# blimpy-2_1.net
KiCad netlist of a schematic drawn in EAGLE
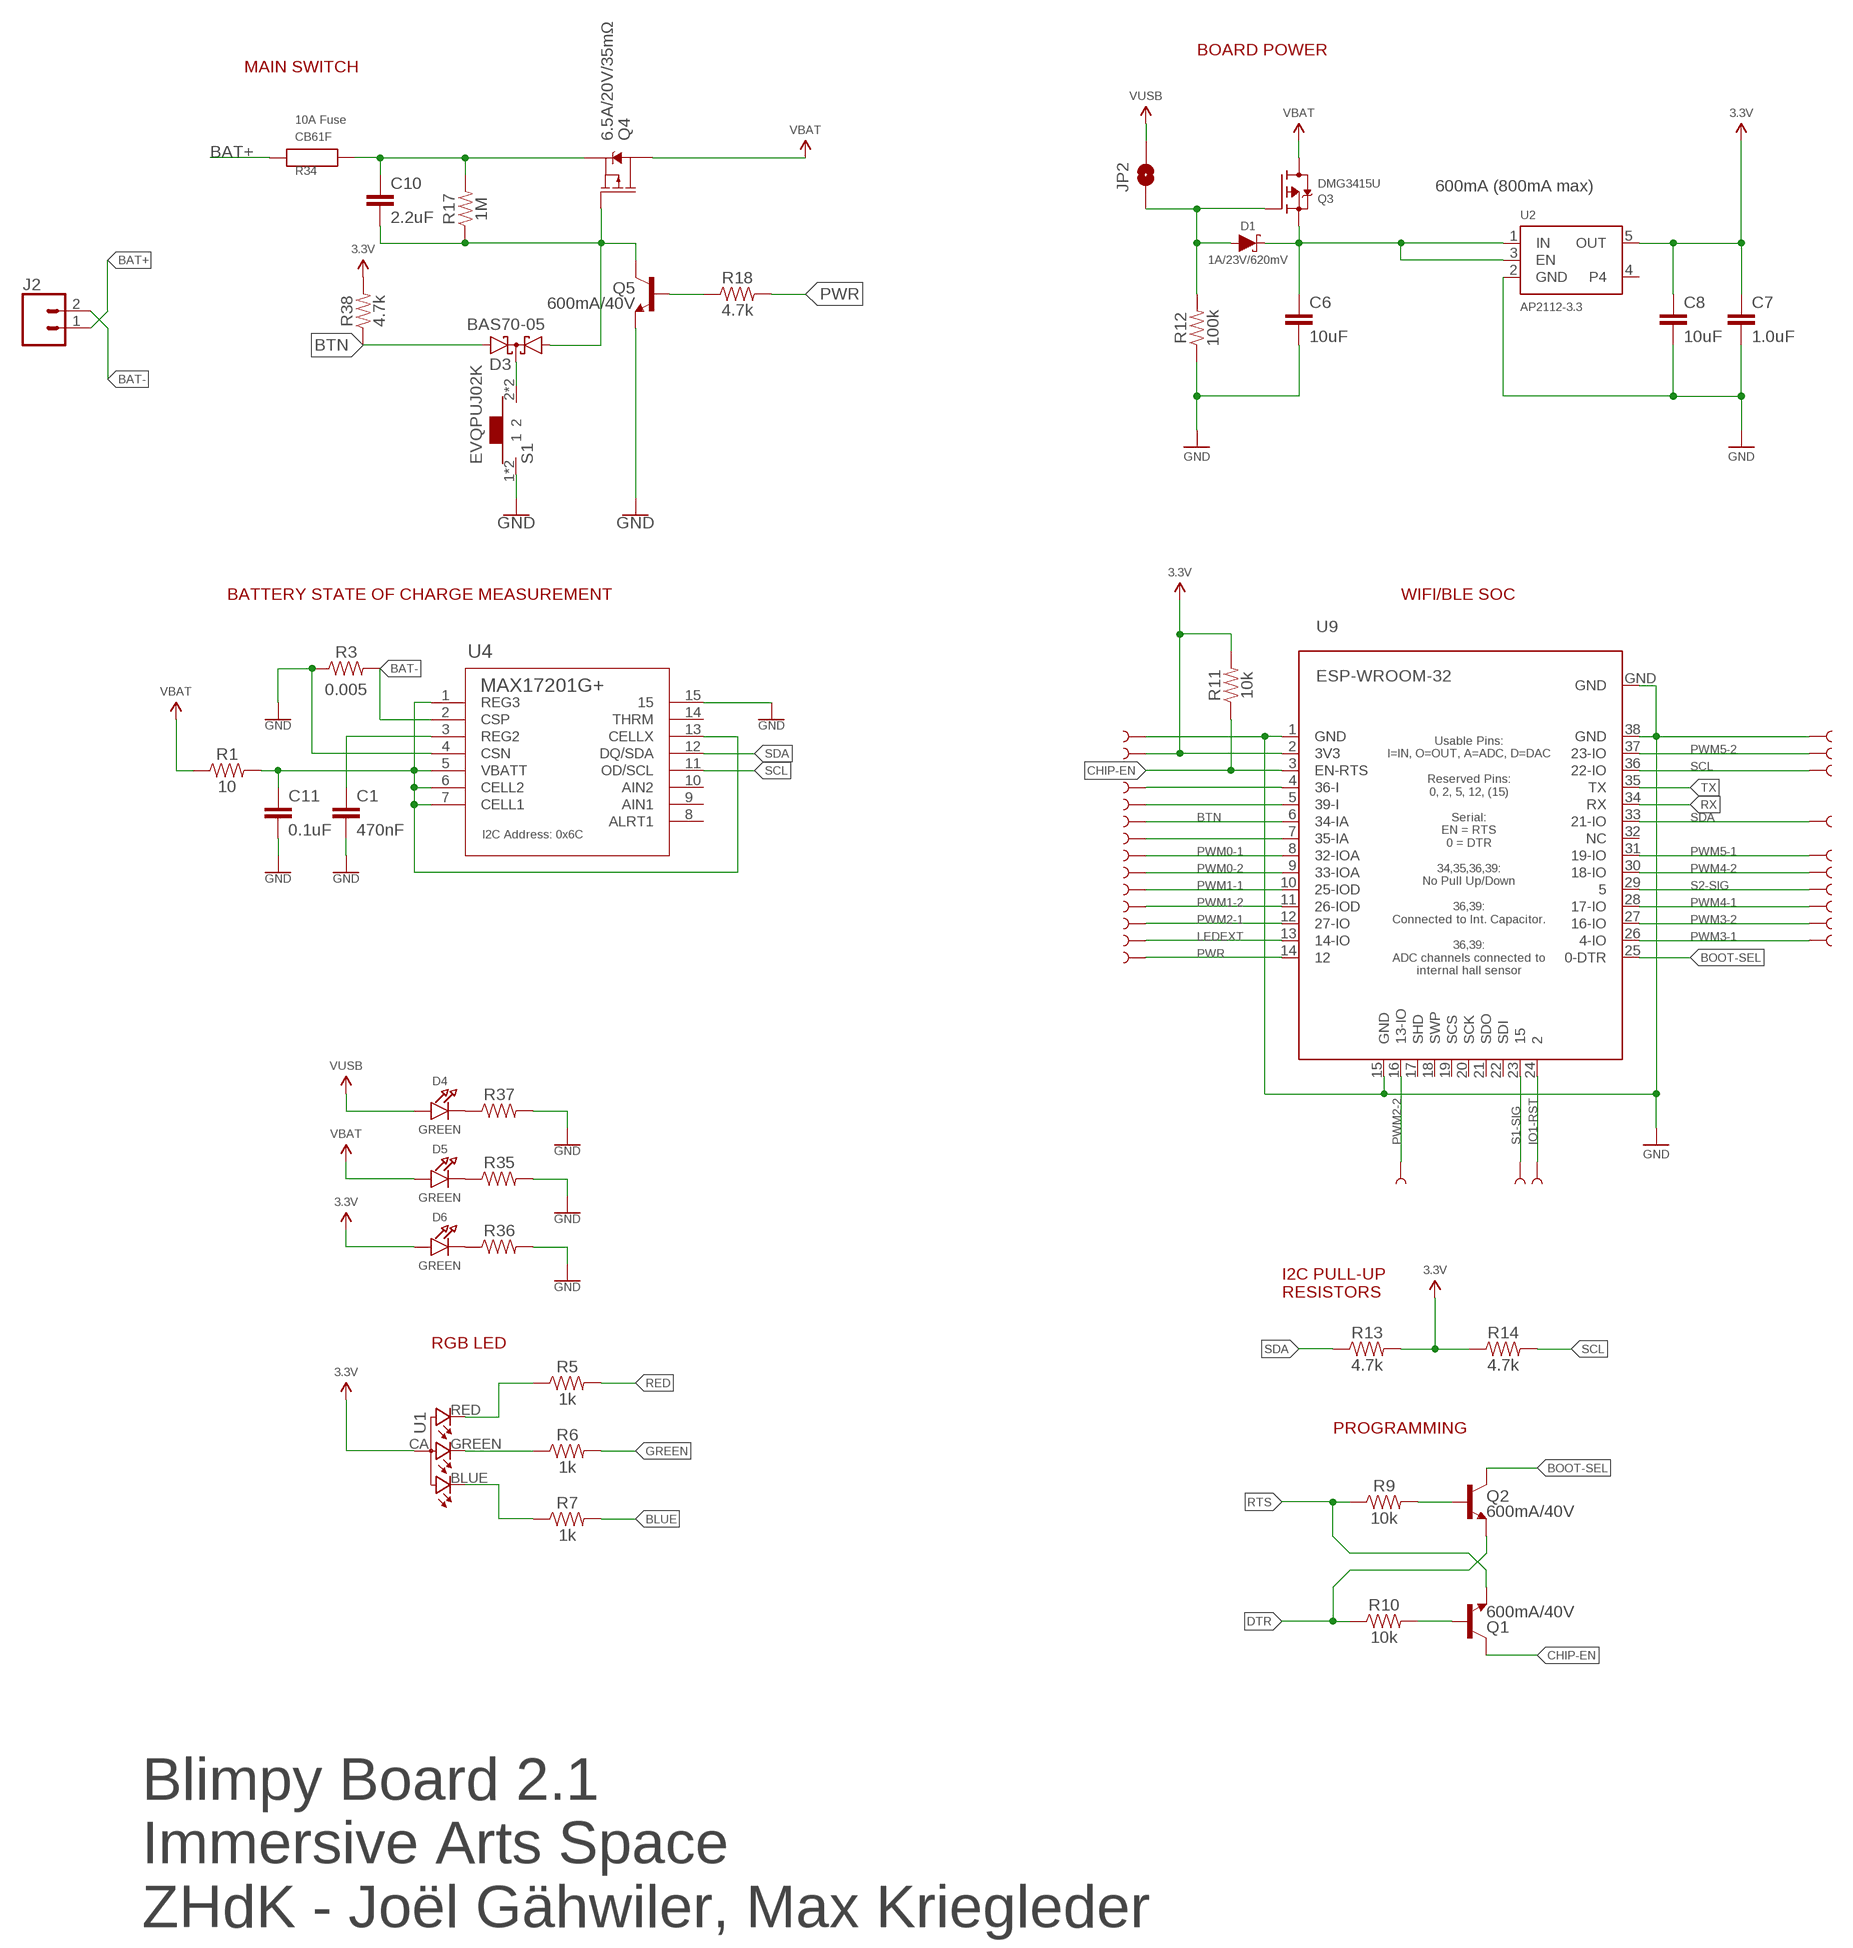
[diagram p0: schematic, sheet 1, part 1 of 2]
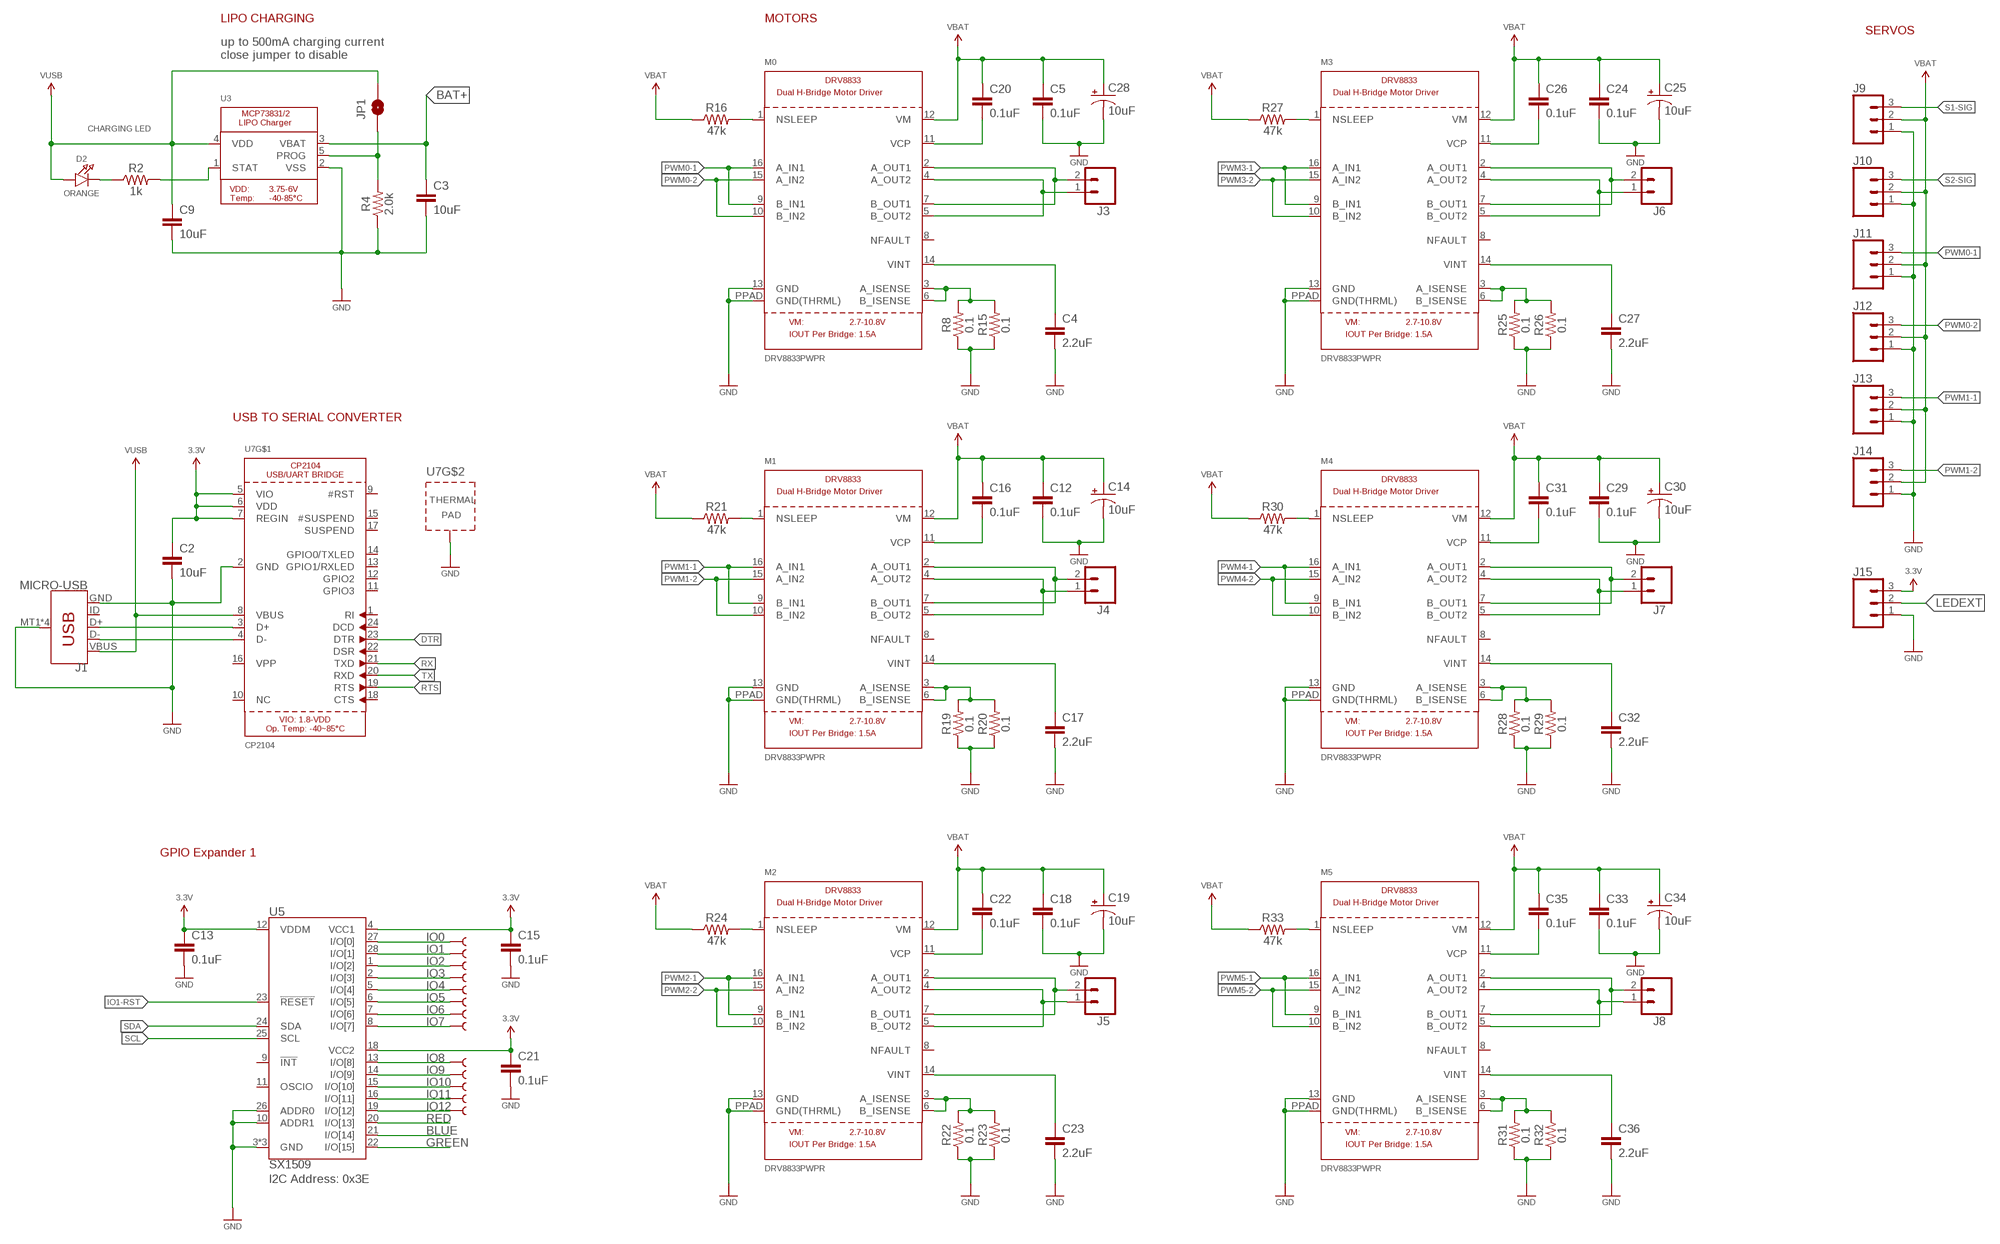
[diagram p1: schematic, sheet 1, part 2 of 2]

(export (version "E")
  (design (tool "Eeschema 10.0.6"))
  (components
    (comp (ref "C1")
      (value "470nF")
      (footprint "eagle-import:0603")
      (libsource (lib "eagle-import") (part "470NF-0608"))
    )
    (comp (ref "C2")
      (value "10uF")
      (footprint "eagle-import:0603")
      (libsource (lib "eagle-import") (part "10UF-0603-6.3V-20%"))
    )
    (comp (ref "C3")
      (value "10uF")
      (footprint "eagle-import:0603")
      (libsource (lib "eagle-import") (part "10UF-0603-6.3V-20%"))
    )
    (comp (ref "C4")
      (value "2.2uF")
      (footprint "eagle-import:0603")
      (libsource (lib "eagle-import") (part "2.2UF-0603-10V-20%"))
    )
    (comp (ref "C5")
      (value "0.1uF")
      (footprint "eagle-import:0603")
      (libsource (lib "eagle-import") (part "0.1UF-0603-25V-5%"))
    )
    (comp (ref "C6")
      (value "10uF")
      (footprint "eagle-import:0603")
      (libsource (lib "eagle-import") (part "10UF-0603-6.3V-20%"))
    )
    (comp (ref "C7")
      (value "1.0uF")
      (footprint "eagle-import:0603")
      (libsource (lib "eagle-import") (part "1.0UF-0603-16V-10%"))
    )
    (comp (ref "C8")
      (value "10uF")
      (footprint "eagle-import:0603")
      (libsource (lib "eagle-import") (part "10UF-0603-6.3V-20%"))
    )
    (comp (ref "C9")
      (value "10uF")
      (footprint "eagle-import:0603")
      (libsource (lib "eagle-import") (part "10UF-0603-6.3V-20%"))
    )
    (comp (ref "C10")
      (value "2.2uF")
      (footprint "eagle-import:0603")
      (libsource (lib "eagle-import") (part "2.2UF-0603-10V-20%"))
    )
    (comp (ref "C11")
      (value "0.1uF")
      (footprint "eagle-import:0603")
      (libsource (lib "eagle-import") (part "SparkFun-Capacitors_510_0.1UF-0603-25V-5%"))
    )
    (comp (ref "C12")
      (value "0.1uF")
      (footprint "eagle-import:0603")
      (libsource (lib "eagle-import") (part "0.1UF-0603-25V-5%"))
    )
    (comp (ref "C13")
      (value "0.1uF")
      (footprint "eagle-import:0603")
      (libsource (lib "eagle-import") (part "0.1UF-0603-25V-5%"))
    )
    (comp (ref "C14")
      (value "10uF")
      (footprint "eagle-import:EIA3216")
      (libsource (lib "eagle-import") (part "10UF-POLAR-EIA3216-16V-10%(TANT)"))
    )
    (comp (ref "C15")
      (value "0.1uF")
      (footprint "eagle-import:0603")
      (libsource (lib "eagle-import") (part "SparkFun-Capacitors_510_0.1UF-0603-25V-5%"))
    )
    (comp (ref "C16")
      (value "0.1uF")
      (footprint "eagle-import:0603")
      (libsource (lib "eagle-import") (part "0.1UF-0603-25V-5%"))
    )
    (comp (ref "C17")
      (value "2.2uF")
      (footprint "eagle-import:0603")
      (libsource (lib "eagle-import") (part "2.2UF-0603-10V-20%"))
    )
    (comp (ref "C18")
      (value "0.1uF")
      (footprint "eagle-import:0603")
      (libsource (lib "eagle-import") (part "0.1UF-0603-25V-5%"))
    )
    (comp (ref "C19")
      (value "10uF")
      (footprint "eagle-import:EIA3216")
      (libsource (lib "eagle-import") (part "10UF-POLAR-EIA3216-16V-10%(TANT)"))
    )
    (comp (ref "C20")
      (value "0.1uF")
      (footprint "eagle-import:0603")
      (libsource (lib "eagle-import") (part "0.1UF-0603-25V-5%"))
    )
    (comp (ref "C21")
      (value "0.1uF")
      (footprint "eagle-import:0603")
      (libsource (lib "eagle-import") (part "0.1UF-0603-25V-5%"))
    )
    (comp (ref "C22")
      (value "0.1uF")
      (footprint "eagle-import:0603")
      (libsource (lib "eagle-import") (part "0.1UF-0603-25V-5%"))
    )
    (comp (ref "C23")
      (value "2.2uF")
      (footprint "eagle-import:0603")
      (libsource (lib "eagle-import") (part "2.2UF-0603-10V-20%"))
    )
    (comp (ref "C24")
      (value "0.1uF")
      (footprint "eagle-import:0603")
      (libsource (lib "eagle-import") (part "0.1UF-0603-25V-5%"))
    )
    (comp (ref "C25")
      (value "10uF")
      (footprint "eagle-import:EIA3216")
      (libsource (lib "eagle-import") (part "10UF-POLAR-EIA3216-16V-10%(TANT)"))
    )
    (comp (ref "C26")
      (value "0.1uF")
      (footprint "eagle-import:0603")
      (libsource (lib "eagle-import") (part "0.1UF-0603-25V-5%"))
    )
    (comp (ref "C27")
      (value "2.2uF")
      (footprint "eagle-import:0603")
      (libsource (lib "eagle-import") (part "2.2UF-0603-10V-20%"))
    )
    (comp (ref "C28")
      (value "10uF")
      (footprint "eagle-import:EIA3216")
      (libsource (lib "eagle-import") (part "10UF-POLAR-EIA3216-16V-10%(TANT)"))
    )
    (comp (ref "C29")
      (value "0.1uF")
      (footprint "eagle-import:0603")
      (libsource (lib "eagle-import") (part "0.1UF-0603-25V-5%"))
    )
    (comp (ref "C30")
      (value "10uF")
      (footprint "eagle-import:EIA3216")
      (libsource (lib "eagle-import") (part "10UF-POLAR-EIA3216-16V-10%(TANT)"))
    )
    (comp (ref "C31")
      (value "0.1uF")
      (footprint "eagle-import:0603")
      (libsource (lib "eagle-import") (part "0.1UF-0603-25V-5%"))
    )
    (comp (ref "C32")
      (value "2.2uF")
      (footprint "eagle-import:0603")
      (libsource (lib "eagle-import") (part "2.2UF-0603-10V-20%"))
    )
    (comp (ref "C33")
      (value "0.1uF")
      (footprint "eagle-import:0603")
      (libsource (lib "eagle-import") (part "0.1UF-0603-25V-5%"))
    )
    (comp (ref "C34")
      (value "10uF")
      (footprint "eagle-import:EIA3216")
      (libsource (lib "eagle-import") (part "10UF-POLAR-EIA3216-16V-10%(TANT)"))
    )
    (comp (ref "C35")
      (value "0.1uF")
      (footprint "eagle-import:0603")
      (libsource (lib "eagle-import") (part "0.1UF-0603-25V-5%"))
    )
    (comp (ref "C36")
      (value "2.2uF")
      (footprint "eagle-import:0603")
      (libsource (lib "eagle-import") (part "2.2UF-0603-10V-20%"))
    )
    (comp (ref "D1")
      (value "1A/23V/620mV")
      (footprint "eagle-import:SOD-323")
      (libsource (lib "eagle-import") (part "DIODE-SCHOTTKY-BAT20J"))
    )
    (comp (ref "D2")
      (value "ORANGE")
      (footprint "eagle-import:CHIPLED_0805_NOOUTLINE")
      (libsource (lib "eagle-import") (part "LED0805_NOOUTLINE"))
    )
    (comp (ref "D3")
      (value "BAS70-05")
      (footprint "eagle-import:SOT23")
      (libsource (lib "eagle-import") (part "BAS70-05"))
    )
    (comp (ref "D4")
      (value "GREEN")
      (footprint "eagle-import:CHIPLED_0805_NOOUTLINE")
      (libsource (lib "eagle-import") (part "LED0805_NOOUTLINE"))
    )
    (comp (ref "D5")
      (value "GREEN")
      (footprint "eagle-import:CHIPLED_0805_NOOUTLINE")
      (libsource (lib "eagle-import") (part "LED0805_NOOUTLINE"))
    )
    (comp (ref "D6")
      (value "GREEN")
      (footprint "eagle-import:CHIPLED_0805_NOOUTLINE")
      (libsource (lib "eagle-import") (part "LED0805_NOOUTLINE"))
    )
    (comp (ref "J1")
      (value "MICRO-USB")
      (footprint "eagle-import:USB-MICROB")
      (libsource (lib "eagle-import") (part "USB_MICRO-B_SMT"))
    )
    (comp (ref "J2")
      (value "CONN_02PTH4")
      (footprint "eagle-import:1X02_XTRA_BIG")
      (libsource (lib "eagle-import") (part "CONN_02PTH4"))
    )
    (comp (ref "J3")
      (value "CONN_02-JST-2MM-SMT")
      (footprint "eagle-import:JST-2-SMD")
      (libsource (lib "eagle-import") (part "CONN_02-JST-2MM-SMT"))
    )
    (comp (ref "J4")
      (value "CONN_02-JST-2MM-SMT")
      (footprint "eagle-import:JST-2-SMD")
      (libsource (lib "eagle-import") (part "CONN_02-JST-2MM-SMT"))
    )
    (comp (ref "J5")
      (value "CONN_02-JST-2MM-SMT")
      (footprint "eagle-import:JST-2-SMD")
      (libsource (lib "eagle-import") (part "CONN_02-JST-2MM-SMT"))
    )
    (comp (ref "J6")
      (value "CONN_02-JST-2MM-SMT")
      (footprint "eagle-import:JST-2-SMD")
      (libsource (lib "eagle-import") (part "CONN_02-JST-2MM-SMT"))
    )
    (comp (ref "J7")
      (value "CONN_02-JST-2MM-SMT")
      (footprint "eagle-import:JST-2-SMD")
      (libsource (lib "eagle-import") (part "CONN_02-JST-2MM-SMT"))
    )
    (comp (ref "J8")
      (value "CONN_02-JST-2MM-SMT")
      (footprint "eagle-import:JST-2-SMD")
      (libsource (lib "eagle-import") (part "CONN_02-JST-2MM-SMT"))
    )
    (comp (ref "J9")
      (value "3-PIN SMD")
      (footprint "eagle-import:JST-3-SMD")
      (libsource (lib "eagle-import") (part "CONN_03JST-SMD"))
    )
    (comp (ref "J10")
      (value "3-PIN SMD")
      (footprint "eagle-import:JST-3-SMD")
      (libsource (lib "eagle-import") (part "CONN_03JST-SMD"))
    )
    (comp (ref "J11")
      (value "3-PIN SMD")
      (footprint "eagle-import:JST-3-SMD")
      (libsource (lib "eagle-import") (part "CONN_03JST-SMD"))
    )
    (comp (ref "J12")
      (value "3-PIN SMD")
      (footprint "eagle-import:JST-3-SMD")
      (libsource (lib "eagle-import") (part "CONN_03JST-SMD"))
    )
    (comp (ref "J13")
      (value "3-PIN SMD")
      (footprint "eagle-import:JST-3-SMD")
      (libsource (lib "eagle-import") (part "CONN_03JST-SMD"))
    )
    (comp (ref "J14")
      (value "3-PIN SMD")
      (footprint "eagle-import:JST-3-SMD")
      (libsource (lib "eagle-import") (part "CONN_03JST-SMD"))
    )
    (comp (ref "J15")
      (value "3-PIN SMD")
      (footprint "eagle-import:JST-3-SMD")
      (libsource (lib "eagle-import") (part "CONN_03JST-SMD"))
    )
    (comp (ref "JP1")
      (value "JUMPER-SMT_2_NO_SILK")
      (footprint "eagle-import:SMT-JUMPER_2_NO_SILK")
      (libsource (lib "eagle-import") (part "JUMPER-SMT_2_NO_SILK"))
    )
    (comp (ref "JP2")
      (value "JUMPER-SMT_2_NO_SILK")
      (footprint "eagle-import:SMT-JUMPER_2_NO_SILK")
      (libsource (lib "eagle-import") (part "JUMPER-SMT_2_NO_SILK"))
    )
    (comp (ref "M0")
      (value "DRV8833PWPR")
      (footprint "eagle-import:HTSSOP16")
      (libsource (lib "eagle-import") (part "DRV8833"))
    )
    (comp (ref "M1")
      (value "DRV8833PWPR")
      (footprint "eagle-import:HTSSOP16")
      (libsource (lib "eagle-import") (part "DRV8833"))
    )
    (comp (ref "M2")
      (value "DRV8833PWPR")
      (footprint "eagle-import:HTSSOP16")
      (libsource (lib "eagle-import") (part "DRV8833"))
    )
    (comp (ref "M3")
      (value "DRV8833PWPR")
      (footprint "eagle-import:HTSSOP16")
      (libsource (lib "eagle-import") (part "DRV8833"))
    )
    (comp (ref "M4")
      (value "DRV8833PWPR")
      (footprint "eagle-import:HTSSOP16")
      (libsource (lib "eagle-import") (part "DRV8833"))
    )
    (comp (ref "M5")
      (value "DRV8833PWPR")
      (footprint "eagle-import:HTSSOP16")
      (libsource (lib "eagle-import") (part "DRV8833"))
    )
    (comp (ref "Q1")
      (value "600mA/40V")
      (footprint "eagle-import:SOT23-3")
      (libsource (lib "eagle-import") (part "TRANS_NPN-MMBT2222AL"))
    )
    (comp (ref "Q2")
      (value "600mA/40V")
      (footprint "eagle-import:SOT23-3")
      (libsource (lib "eagle-import") (part "TRANS_NPN-MMBT2222AL"))
    )
    (comp (ref "Q3")
      (value "DMG3415U")
      (footprint "eagle-import:SOT23-R")
      (libsource (lib "eagle-import") (part "MOSFET-P"))
    )
    (comp (ref "Q4")
      (value "6.5A/20V/35mΩ")
      (footprint "eagle-import:SO08")
      (libsource (lib "eagle-import") (part "MOSFET_PCH-NDS8434"))
    )
    (comp (ref "Q5")
      (value "600mA/40V")
      (footprint "eagle-import:SOT23-3")
      (libsource (lib "eagle-import") (part "TRANS_NPN-MMBT2222AL"))
    )
    (comp (ref "R1")
      (value "10")
      (footprint "eagle-import:0603")
      (libsource (lib "eagle-import") (part "10OHM-0603-1/10W-1%"))
    )
    (comp (ref "R2")
      (value "1k")
      (footprint "eagle-import:0603")
      (libsource (lib "eagle-import") (part "1KOHM-0603-1/10W-1%"))
    )
    (comp (ref "R3")
      (value "0.005")
      (footprint "eagle-import:1206")
      (libsource (lib "eagle-import") (part "RESISTOR1206"))
    )
    (comp (ref "R4")
      (value "2.0k")
      (footprint "eagle-import:0603")
      (libsource (lib "eagle-import") (part "2.0KOHM-0603-1/10W-5%"))
    )
    (comp (ref "R5")
      (value "1k")
      (footprint "eagle-import:0603")
      (libsource (lib "eagle-import") (part "1KOHM-0603-1/10W-1%"))
    )
    (comp (ref "R6")
      (value "1k")
      (footprint "eagle-import:0603")
      (libsource (lib "eagle-import") (part "1KOHM-0603-1/10W-1%"))
    )
    (comp (ref "R7")
      (value "1k")
      (footprint "eagle-import:0603")
      (libsource (lib "eagle-import") (part "1KOHM-0603-1/10W-1%"))
    )
    (comp (ref "R8")
      (value "0.1")
      (footprint "eagle-import:1206")
      (libsource (lib "eagle-import") (part "RESISTOR1206"))
    )
    (comp (ref "R9")
      (value "10k")
      (footprint "eagle-import:0603")
      (libsource (lib "eagle-import") (part "10KOHM-0603-1/10W-1%"))
    )
    (comp (ref "R10")
      (value "10k")
      (footprint "eagle-import:0603")
      (libsource (lib "eagle-import") (part "10KOHM-0603-1/10W-1%"))
    )
    (comp (ref "R11")
      (value "10k")
      (footprint "eagle-import:0603")
      (libsource (lib "eagle-import") (part "10KOHM-0603-1/10W-1%"))
    )
    (comp (ref "R12")
      (value "100k")
      (footprint "eagle-import:0603")
      (libsource (lib "eagle-import") (part "100KOHM-0603-1/10W-1%"))
    )
    (comp (ref "R13")
      (value "4.7k")
      (footprint "eagle-import:0603")
      (libsource (lib "eagle-import") (part "4.7KOHM-0603-1/10W-1%"))
    )
    (comp (ref "R14")
      (value "4.7k")
      (footprint "eagle-import:0603")
      (libsource (lib "eagle-import") (part "4.7KOHM-0603-1/10W-1%"))
    )
    (comp (ref "R15")
      (value "0.1")
      (footprint "eagle-import:1206")
      (libsource (lib "eagle-import") (part "RESISTOR1206"))
    )
    (comp (ref "R16")
      (value "47k")
      (footprint "eagle-import:0603")
      (libsource (lib "eagle-import") (part "47KOHM-0603-1/10W-1%"))
    )
    (comp (ref "R17")
      (value "1M")
      (footprint "eagle-import:0603")
      (libsource (lib "eagle-import") (part "1MOHM-0603-1/4W-5%"))
    )
    (comp (ref "R18")
      (value "4.7k")
      (footprint "eagle-import:0603")
      (libsource (lib "eagle-import") (part "SparkFun-Resistors_532_4.7KOHM-0603-1/10W-1%"))
    )
    (comp (ref "R19")
      (value "0.1")
      (footprint "eagle-import:1206")
      (libsource (lib "eagle-import") (part "RESISTOR1206"))
    )
    (comp (ref "R20")
      (value "0.1")
      (footprint "eagle-import:1206")
      (libsource (lib "eagle-import") (part "RESISTOR1206"))
    )
    (comp (ref "R21")
      (value "47k")
      (footprint "eagle-import:0603")
      (libsource (lib "eagle-import") (part "47KOHM-0603-1/10W-1%"))
    )
    (comp (ref "R22")
      (value "0.1")
      (footprint "eagle-import:1206")
      (libsource (lib "eagle-import") (part "RESISTOR1206"))
    )
    (comp (ref "R23")
      (value "0.1")
      (footprint "eagle-import:1206")
      (libsource (lib "eagle-import") (part "RESISTOR1206"))
    )
    (comp (ref "R24")
      (value "47k")
      (footprint "eagle-import:0603")
      (libsource (lib "eagle-import") (part "47KOHM-0603-1/10W-1%"))
    )
    (comp (ref "R25")
      (value "0.1")
      (footprint "eagle-import:1206")
      (libsource (lib "eagle-import") (part "RESISTOR1206"))
    )
    (comp (ref "R26")
      (value "0.1")
      (footprint "eagle-import:1206")
      (libsource (lib "eagle-import") (part "RESISTOR1206"))
    )
    (comp (ref "R27")
      (value "47k")
      (footprint "eagle-import:0603")
      (libsource (lib "eagle-import") (part "47KOHM-0603-1/10W-1%"))
    )
    (comp (ref "R28")
      (value "0.1")
      (footprint "eagle-import:1206")
      (libsource (lib "eagle-import") (part "RESISTOR1206"))
    )
    (comp (ref "R29")
      (value "0.1")
      (footprint "eagle-import:1206")
      (libsource (lib "eagle-import") (part "RESISTOR1206"))
    )
    (comp (ref "R30")
      (value "47k")
      (footprint "eagle-import:0603")
      (libsource (lib "eagle-import") (part "47KOHM-0603-1/10W-1%"))
    )
    (comp (ref "R31")
      (value "0.1")
      (footprint "eagle-import:1206")
      (libsource (lib "eagle-import") (part "RESISTOR1206"))
    )
    (comp (ref "R32")
      (value "0.1")
      (footprint "eagle-import:1206")
      (libsource (lib "eagle-import") (part "RESISTOR1206"))
    )
    (comp (ref "R33")
      (value "47k")
      (footprint "eagle-import:0603")
      (libsource (lib "eagle-import") (part "47KOHM-0603-1/10W-1%"))
    )
    (comp (ref "R34")
      (value "CB61F")
      (footprint "eagle-import:CB61F")
      (libsource (lib "eagle-import") (part "CB61F"))
    )
    (comp (ref "R35")
      (value "RESISTOR0603")
      (footprint "eagle-import:0603")
      (libsource (lib "eagle-import") (part "RESISTOR0603"))
    )
    (comp (ref "R36")
      (value "RESISTOR0603")
      (footprint "eagle-import:0603")
      (libsource (lib "eagle-import") (part "RESISTOR0603"))
    )
    (comp (ref "R37")
      (value "RESISTOR0603")
      (footprint "eagle-import:0603")
      (libsource (lib "eagle-import") (part "RESISTOR0603"))
    )
    (comp (ref "R38")
      (value "4.7k")
      (footprint "eagle-import:0603")
      (libsource (lib "eagle-import") (part "1MOHM-0603-1/4W-5%"))
    )
    (comp (ref "S1")
      (value "EVQPUJ02K")
      (footprint "eagle-import:EVQPUJ02K")
      (libsource (lib "eagle-import") (part "EVQPUJ02K"))
    )
    (comp (ref "TP1")
      (value "TEST-POINT3")
      (footprint "eagle-import:PAD.03X.03")
      (libsource (lib "eagle-import") (part "TEST-POINT3"))
    )
    (comp (ref "TP2")
      (value "TEST-POINT3")
      (footprint "eagle-import:PAD.03X.03")
      (libsource (lib "eagle-import") (part "TEST-POINT3"))
    )
    (comp (ref "TP3")
      (value "TEST-POINT3")
      (footprint "eagle-import:PAD.03X.03")
      (libsource (lib "eagle-import") (part "TEST-POINT3"))
    )
    (comp (ref "TP4")
      (value "TEST-POINT3")
      (footprint "eagle-import:PAD.03X.03")
      (libsource (lib "eagle-import") (part "TEST-POINT3"))
    )
    (comp (ref "TP5")
      (value "TEST-POINT3")
      (footprint "eagle-import:PAD.03X.03")
      (libsource (lib "eagle-import") (part "TEST-POINT3"))
    )
    (comp (ref "TP6")
      (value "TEST-POINT3")
      (footprint "eagle-import:PAD.03X.03")
      (libsource (lib "eagle-import") (part "TEST-POINT3"))
    )
    (comp (ref "TP7")
      (value "TEST-POINT3")
      (footprint "eagle-import:PAD.03X.03")
      (libsource (lib "eagle-import") (part "TEST-POINT3"))
    )
    (comp (ref "TP8")
      (value "TEST-POINT3")
      (footprint "eagle-import:PAD.03X.03")
      (libsource (lib "eagle-import") (part "TEST-POINT3"))
    )
    (comp (ref "TP9")
      (value "TEST-POINT3")
      (footprint "eagle-import:PAD.03X.03")
      (libsource (lib "eagle-import") (part "TEST-POINT3"))
    )
    (comp (ref "TP10")
      (value "TEST-POINT3")
      (footprint "eagle-import:PAD.03X.03")
      (libsource (lib "eagle-import") (part "TEST-POINT3"))
    )
    (comp (ref "TP11")
      (value "TEST-POINT3")
      (footprint "eagle-import:PAD.03X.03")
      (libsource (lib "eagle-import") (part "TEST-POINT3"))
    )
    (comp (ref "TP12")
      (value "TEST-POINT3")
      (footprint "eagle-import:PAD.03X.03")
      (libsource (lib "eagle-import") (part "TEST-POINT3"))
    )
    (comp (ref "TP13")
      (value "TEST-POINT3")
      (footprint "eagle-import:PAD.03X.03")
      (libsource (lib "eagle-import") (part "TEST-POINT3"))
    )
    (comp (ref "TP14")
      (value "TEST-POINT3")
      (footprint "eagle-import:PAD.03X.03")
      (libsource (lib "eagle-import") (part "TEST-POINT3"))
    )
    (comp (ref "TP15")
      (value "TEST-POINT3")
      (footprint "eagle-import:PAD.03X.03")
      (libsource (lib "eagle-import") (part "TEST-POINT3"))
    )
    (comp (ref "TP16")
      (value "TEST-POINT3")
      (footprint "eagle-import:PAD.03X.03")
      (libsource (lib "eagle-import") (part "TEST-POINT3"))
    )
    (comp (ref "TP17")
      (value "TEST-POINT3")
      (footprint "eagle-import:PAD.03X.03")
      (libsource (lib "eagle-import") (part "TEST-POINT3"))
    )
    (comp (ref "TP18")
      (value "TEST-POINT3")
      (footprint "eagle-import:PAD.03X.03")
      (libsource (lib "eagle-import") (part "TEST-POINT3"))
    )
    (comp (ref "TP19")
      (value "TEST-POINT3")
      (footprint "eagle-import:PAD.03X.03")
      (libsource (lib "eagle-import") (part "TEST-POINT3"))
    )
    (comp (ref "TP20")
      (value "TEST-POINT3")
      (footprint "eagle-import:PAD.03X.03")
      (libsource (lib "eagle-import") (part "TEST-POINT3"))
    )
    (comp (ref "TP21")
      (value "TEST-POINT3")
      (footprint "eagle-import:PAD.03X.03")
      (libsource (lib "eagle-import") (part "TEST-POINT3"))
    )
    (comp (ref "TP22")
      (value "TEST-POINT3")
      (footprint "eagle-import:PAD.03X.03")
      (libsource (lib "eagle-import") (part "TEST-POINT3"))
    )
    (comp (ref "TP23")
      (value "TEST-POINT3")
      (footprint "eagle-import:PAD.03X.03")
      (libsource (lib "eagle-import") (part "TEST-POINT3"))
    )
    (comp (ref "TP24")
      (value "TEST-POINT3")
      (footprint "eagle-import:PAD.03X.03")
      (libsource (lib "eagle-import") (part "TEST-POINT3"))
    )
    (comp (ref "TP25")
      (value "TEST-POINT3")
      (footprint "eagle-import:PAD.03X.03")
      (libsource (lib "eagle-import") (part "TEST-POINT3"))
    )
    (comp (ref "TP26")
      (value "TEST-POINT3")
      (footprint "eagle-import:PAD.03X.03")
      (libsource (lib "eagle-import") (part "TEST-POINT3"))
    )
    (comp (ref "TP27")
      (value "TEST-POINT3")
      (footprint "eagle-import:PAD.03X.03")
      (libsource (lib "eagle-import") (part "TEST-POINT3"))
    )
    (comp (ref "TP28")
      (value "TEST-POINT3")
      (footprint "eagle-import:PAD.03X.03")
      (libsource (lib "eagle-import") (part "TEST-POINT3"))
    )
    (comp (ref "TP29")
      (value "TEST-POINT3")
      (footprint "eagle-import:PAD.03X.03")
      (libsource (lib "eagle-import") (part "TEST-POINT3"))
    )
    (comp (ref "TP30")
      (value "TEST-POINT3")
      (footprint "eagle-import:PAD.03X.03")
      (libsource (lib "eagle-import") (part "TEST-POINT3"))
    )
    (comp (ref "TP31")
      (value "TEST-POINT3")
      (footprint "eagle-import:PAD.03X.03")
      (libsource (lib "eagle-import") (part "TEST-POINT3"))
    )
    (comp (ref "TP32")
      (value "TEST-POINT3")
      (footprint "eagle-import:PAD.03X.03")
      (libsource (lib "eagle-import") (part "TEST-POINT3"))
    )
    (comp (ref "TP33")
      (value "TEST-POINT3")
      (footprint "eagle-import:PAD.03X.03")
      (libsource (lib "eagle-import") (part "TEST-POINT3"))
    )
    (comp (ref "TP34")
      (value "TEST-POINT3")
      (footprint "eagle-import:PAD.03X.03")
      (libsource (lib "eagle-import") (part "TEST-POINT3"))
    )
    (comp (ref "TP35")
      (value "TEST-POINT3")
      (footprint "eagle-import:PAD.03X.03")
      (libsource (lib "eagle-import") (part "TEST-POINT3"))
    )
    (comp (ref "TP36")
      (value "TEST-POINT3")
      (footprint "eagle-import:PAD.03X.03")
      (libsource (lib "eagle-import") (part "TEST-POINT3"))
    )
    (comp (ref "TP37")
      (value "TEST-POINT3")
      (footprint "eagle-import:PAD.03X.03")
      (libsource (lib "eagle-import") (part "TEST-POINT3"))
    )
    (comp (ref "TP38")
      (value "TEST-POINT3")
      (footprint "eagle-import:PAD.03X.03")
      (libsource (lib "eagle-import") (part "TEST-POINT3"))
    )
    (comp (ref "TP39")
      (value "TEST-POINT3")
      (footprint "eagle-import:PAD.03X.03")
      (libsource (lib "eagle-import") (part "TEST-POINT3"))
    )
    (comp (ref "U1")
      (value "PARTICLE_RGB-LED-CLMVB-FKARGB")
      (footprint "eagle-import:PARTICLE_PLCC4-2MM-RGB")
      (libsource (lib "eagle-import") (part "PARTICLE_RGB-LED-CLMVB-FKARGB"))
    )
    (comp (ref "U2")
      (value "AP2112-3.3")
      (footprint "eagle-import:SOT23-5")
      (libsource (lib "eagle-import") (part "VREG_SOT23-5"))
    )
    (comp (ref "U3")
      (value "MICROBUILDER_MCP73831/2")
      (footprint "eagle-import:MICROBUILDER_SOT23-5")
      (libsource (lib "eagle-import") (part "MICROBUILDER_MCP73831/2"))
    )
    (comp (ref "U4")
      (value "MAX17201G+")
      (footprint "eagle-import:21-0137I_T1433-1_MXM")
      (fields (field (name "COPYRIGHT") "Copyright (C) 2018 Accelerated Designs. All rights reserved"))
      (libsource (lib "eagle-import") (part "MAX17201G+"))
    )
    (comp (ref "U5")
      (value "SX1509")
      (footprint "eagle-import:QFN-28")
      (libsource (lib "eagle-import") (part "SX1509"))
    )
    (comp (ref "U7")
      (value "CP2104")
      (footprint "eagle-import:QFN24_4MM_SMSC")
      (libsource (lib "eagle-import") (part "CP2104"))
    )
    (comp (ref "U9")
      (value "ESP-WROOM-32")
      (footprint "eagle-import:ESP-WROOM-32")
      (libsource (lib "eagle-import") (part "ESP-WROOM-32"))
    )
  )
  (nets
    (net (code "1") (name "/IO0") (class "Default")
      (node (ref "TP27") (pin "P$1") (pinfunction "1_P$1") (pintype "bidirectional"))
      (node (ref "U5") (pin "27") (pinfunction "I/O[0]_27") (pintype "bidirectional"))
    )
    (net (code "2") (name "/IO1") (class "Default")
      (node (ref "TP28") (pin "P$1") (pinfunction "1_P$1") (pintype "bidirectional"))
      (node (ref "U5") (pin "28") (pinfunction "I/O[1]_28") (pintype "bidirectional"))
    )
    (net (code "3") (name "/IO2") (class "Default")
      (node (ref "TP29") (pin "P$1") (pinfunction "1_P$1") (pintype "bidirectional"))
      (node (ref "U5") (pin "1") (pinfunction "I/O[2]_1") (pintype "bidirectional"))
    )
    (net (code "4") (name "/IO3") (class "Default")
      (node (ref "TP30") (pin "P$1") (pinfunction "1_P$1") (pintype "bidirectional"))
      (node (ref "U5") (pin "2") (pinfunction "I/O[3]_2") (pintype "bidirectional"))
    )
    (net (code "5") (name "/IO4") (class "Default")
      (node (ref "TP31") (pin "P$1") (pinfunction "1_P$1") (pintype "bidirectional"))
      (node (ref "U5") (pin "5") (pinfunction "I/O[4]_5") (pintype "bidirectional"))
    )
    (net (code "6") (name "/IO5") (class "Default")
      (node (ref "TP32") (pin "P$1") (pinfunction "1_P$1") (pintype "bidirectional"))
      (node (ref "U5") (pin "6") (pinfunction "I/O[5]_6") (pintype "bidirectional"))
    )
    (net (code "7") (name "/IO6") (class "Default")
      (node (ref "TP33") (pin "P$1") (pinfunction "1_P$1") (pintype "bidirectional"))
      (node (ref "U5") (pin "7") (pinfunction "I/O[6]_7") (pintype "bidirectional"))
    )
    (net (code "8") (name "/IO7") (class "Default")
      (node (ref "TP34") (pin "P$1") (pinfunction "1_P$1") (pintype "bidirectional"))
      (node (ref "U5") (pin "8") (pinfunction "I/O[7]_8") (pintype "bidirectional"))
    )
    (net (code "9") (name "/IO8") (class "Default")
      (node (ref "TP35") (pin "P$1") (pinfunction "1_P$1") (pintype "bidirectional"))
      (node (ref "U5") (pin "13") (pinfunction "I/O[8]_13") (pintype "bidirectional"))
    )
    (net (code "10") (name "/IO9") (class "Default")
      (node (ref "TP36") (pin "P$1") (pinfunction "1_P$1") (pintype "bidirectional"))
      (node (ref "U5") (pin "14") (pinfunction "I/O[9]_14") (pintype "bidirectional"))
    )
    (net (code "11") (name "/IO10") (class "Default")
      (node (ref "TP37") (pin "P$1") (pinfunction "1_P$1") (pintype "bidirectional"))
      (node (ref "U5") (pin "15") (pinfunction "I/O[10]_15") (pintype "bidirectional"))
    )
    (net (code "12") (name "/IO11") (class "Default")
      (node (ref "TP38") (pin "P$1") (pinfunction "1_P$1") (pintype "bidirectional"))
      (node (ref "U5") (pin "16") (pinfunction "I/O[11]_16") (pintype "bidirectional"))
    )
    (net (code "13") (name "/IO12") (class "Default")
      (node (ref "TP39") (pin "P$1") (pinfunction "1_P$1") (pintype "bidirectional"))
      (node (ref "U5") (pin "19") (pinfunction "I/O[12]_19") (pintype "bidirectional"))
    )
    (net (code "14") (name "3.3V") (class "Default")
      (node (ref "C13") (pin "1") (pinfunction "1_1") (pintype "passive"))
      (node (ref "C15") (pin "1") (pinfunction "1_1") (pintype "passive"))
      (node (ref "C2") (pin "1") (pinfunction "1_1") (pintype "passive"))
      (node (ref "C21") (pin "1") (pinfunction "1_1") (pintype "passive"))
      (node (ref "C7") (pin "1") (pinfunction "1_1") (pintype "passive"))
      (node (ref "C8") (pin "1") (pinfunction "1_1") (pintype "passive"))
      (node (ref "D6") (pin "A") (pinfunction "A_A") (pintype "passive"))
      (node (ref "J15") (pin "3") (pinfunction "3_3") (pintype "passive"))
      (node (ref "R11") (pin "2") (pinfunction "2_2") (pintype "passive"))
      (node (ref "R13") (pin "2") (pinfunction "2_2") (pintype "passive"))
      (node (ref "R14") (pin "1") (pinfunction "1_1") (pintype "passive"))
      (node (ref "R38") (pin "2") (pinfunction "2_2") (pintype "passive"))
      (node (ref "TP11") (pin "P$1") (pinfunction "1_P$1") (pintype "bidirectional"))
      (node (ref "U1") (pin "CA") (pinfunction "1_CA") (pintype "passive"))
      (node (ref "U2") (pin "5") (pinfunction "OUT_5") (pintype "power_in"))
      (node (ref "U5") (pin "12") (pinfunction "VDDM_12") (pintype "bidirectional"))
      (node (ref "U5") (pin "18") (pinfunction "VCC2_18") (pintype "bidirectional"))
      (node (ref "U5") (pin "4") (pinfunction "VCC1_4") (pintype "bidirectional"))
      (node (ref "U7") (pin "5") (pinfunction "VIO_5") (pintype "power_in"))
      (node (ref "U7") (pin "6") (pinfunction "VDD_6") (pintype "power_in"))
      (node (ref "U7") (pin "7") (pinfunction "REGIN_7") (pintype "power_in"))
      (node (ref "U9") (pin "2") (pinfunction "3V3_2") (pintype "bidirectional"))
    )
    (net (code "15") (name "BAT+") (class "Default")
      (node (ref "C3") (pin "1") (pinfunction "1_1") (pintype "passive"))
      (node (ref "J2") (pin "1") (pinfunction "1_1") (pintype "passive"))
      (node (ref "R34") (pin "1") (pinfunction "1_1") (pintype "passive"))
      (node (ref "U3") (pin "3") (pinfunction "VBAT_3") (pintype "power_in"))
    )
    (net (code "16") (name "BAT-") (class "Default")
      (node (ref "J2") (pin "2") (pinfunction "2_2") (pintype "passive"))
      (node (ref "R3") (pin "2") (pinfunction "2_2") (pintype "passive"))
      (node (ref "U4") (pin "2") (pinfunction "CSP_2") (pintype "passive"))
    )
    (net (code "17") (name "BLUE") (class "Default")
      (node (ref "R7") (pin "2") (pinfunction "2_2") (pintype "passive"))
      (node (ref "U5") (pin "21") (pinfunction "I/O[14]_21") (pintype "bidirectional"))
    )
    (net (code "18") (name "BOOT-SEL") (class "Default")
      (node (ref "Q2") (pin "3") (pinfunction "C_3") (pintype "passive"))
      (node (ref "U9") (pin "25") (pinfunction "0-DTR_25") (pintype "bidirectional"))
    )
    (net (code "19") (name "BTN") (class "Default")
      (node (ref "D3") (pin "2") (pinfunction "A2_2") (pintype "passive"))
      (node (ref "R38") (pin "1") (pinfunction "1_1") (pintype "passive"))
      (node (ref "TP8") (pin "P$1") (pinfunction "1_P$1") (pintype "bidirectional"))
      (node (ref "U9") (pin "6") (pinfunction "34-IA_6") (pintype "bidirectional"))
    )
    (net (code "20") (name "CHIP-EN") (class "Default")
      (node (ref "Q1") (pin "3") (pinfunction "C_3") (pintype "passive"))
      (node (ref "R11") (pin "1") (pinfunction "1_1") (pintype "passive"))
      (node (ref "U9") (pin "3") (pinfunction "EN-RTS_3") (pintype "bidirectional"))
    )
    (net (code "21") (name "DTR") (class "Default")
      (node (ref "Q2") (pin "2") (pinfunction "E_2") (pintype "passive"))
      (node (ref "R10") (pin "1") (pinfunction "1_1") (pintype "passive"))
      (node (ref "U7") (pin "23") (pinfunction "DTR_23") (pintype "output"))
    )
    (net (code "22") (name "GND") (class "Default")
      (node (ref "C1") (pin "2") (pinfunction "2_2") (pintype "passive"))
      (node (ref "C11") (pin "2") (pinfunction "2_2") (pintype "passive"))
      (node (ref "C12") (pin "2") (pinfunction "2_2") (pintype "passive"))
      (node (ref "C13") (pin "2") (pinfunction "2_2") (pintype "passive"))
      (node (ref "C14") (pin "-") (pinfunction "-_-") (pintype "passive"))
      (node (ref "C15") (pin "2") (pinfunction "2_2") (pintype "passive"))
      (node (ref "C17") (pin "2") (pinfunction "2_2") (pintype "passive"))
      (node (ref "C18") (pin "2") (pinfunction "2_2") (pintype "passive"))
      (node (ref "C19") (pin "-") (pinfunction "-_-") (pintype "passive"))
      (node (ref "C2") (pin "2") (pinfunction "2_2") (pintype "passive"))
      (node (ref "C21") (pin "2") (pinfunction "2_2") (pintype "passive"))
      (node (ref "C23") (pin "2") (pinfunction "2_2") (pintype "passive"))
      (node (ref "C24") (pin "2") (pinfunction "2_2") (pintype "passive"))
      (node (ref "C25") (pin "-") (pinfunction "-_-") (pintype "passive"))
      (node (ref "C27") (pin "2") (pinfunction "2_2") (pintype "passive"))
      (node (ref "C28") (pin "-") (pinfunction "-_-") (pintype "passive"))
      (node (ref "C29") (pin "2") (pinfunction "2_2") (pintype "passive"))
      (node (ref "C3") (pin "2") (pinfunction "2_2") (pintype "passive"))
      (node (ref "C30") (pin "-") (pinfunction "-_-") (pintype "passive"))
      (node (ref "C32") (pin "2") (pinfunction "2_2") (pintype "passive"))
      (node (ref "C33") (pin "2") (pinfunction "2_2") (pintype "passive"))
      (node (ref "C34") (pin "-") (pinfunction "-_-") (pintype "passive"))
      (node (ref "C36") (pin "2") (pinfunction "2_2") (pintype "passive"))
      (node (ref "C4") (pin "2") (pinfunction "2_2") (pintype "passive"))
      (node (ref "C5") (pin "2") (pinfunction "2_2") (pintype "passive"))
      (node (ref "C6") (pin "2") (pinfunction "2_2") (pintype "passive"))
      (node (ref "C7") (pin "2") (pinfunction "2_2") (pintype "passive"))
      (node (ref "C8") (pin "2") (pinfunction "2_2") (pintype "passive"))
      (node (ref "C9") (pin "2") (pinfunction "2_2") (pintype "passive"))
      (node (ref "J1") (pin "GND") (pinfunction "GND_GND") (pintype "power_in"))
      (node (ref "J1") (pin "MT1") (pinfunction "SHIELD_MT1") (pintype "bidirectional"))
      (node (ref "J1") (pin "MT2") (pinfunction "SHIELD_MT2") (pintype "bidirectional"))
      (node (ref "J1") (pin "P$1") (pinfunction "SHIELD_P$1") (pintype "bidirectional"))
      (node (ref "J1") (pin "P$2") (pinfunction "SHIELD_P$2") (pintype "bidirectional"))
      (node (ref "J10") (pin "1") (pinfunction "1_1") (pintype "passive"))
      (node (ref "J11") (pin "1") (pinfunction "1_1") (pintype "passive"))
      (node (ref "J12") (pin "1") (pinfunction "1_1") (pintype "passive"))
      (node (ref "J13") (pin "1") (pinfunction "1_1") (pintype "passive"))
      (node (ref "J14") (pin "1") (pinfunction "1_1") (pintype "passive"))
      (node (ref "J15") (pin "1") (pinfunction "1_1") (pintype "passive"))
      (node (ref "J9") (pin "1") (pinfunction "1_1") (pintype "passive"))
      (node (ref "M0") (pin "13") (pinfunction "GND_13") (pintype "power_in"))
      (node (ref "M0") (pin "PPAD") (pinfunction "GND(THRML)_PPAD") (pintype "power_in"))
      (node (ref "M1") (pin "13") (pinfunction "GND_13") (pintype "power_in"))
      (node (ref "M1") (pin "PPAD") (pinfunction "GND(THRML)_PPAD") (pintype "power_in"))
      (node (ref "M2") (pin "13") (pinfunction "GND_13") (pintype "power_in"))
      (node (ref "M2") (pin "PPAD") (pinfunction "GND(THRML)_PPAD") (pintype "power_in"))
      (node (ref "M3") (pin "13") (pinfunction "GND_13") (pintype "power_in"))
      (node (ref "M3") (pin "PPAD") (pinfunction "GND(THRML)_PPAD") (pintype "power_in"))
      (node (ref "M4") (pin "13") (pinfunction "GND_13") (pintype "power_in"))
      (node (ref "M4") (pin "PPAD") (pinfunction "GND(THRML)_PPAD") (pintype "power_in"))
      (node (ref "M5") (pin "13") (pinfunction "GND_13") (pintype "power_in"))
      (node (ref "M5") (pin "PPAD") (pinfunction "GND(THRML)_PPAD") (pintype "power_in"))
      (node (ref "Q5") (pin "2") (pinfunction "E_2") (pintype "passive"))
      (node (ref "R12") (pin "1") (pinfunction "1_1") (pintype "passive"))
      (node (ref "R15") (pin "1") (pinfunction "1_1") (pintype "passive"))
      (node (ref "R19") (pin "1") (pinfunction "1_1") (pintype "passive"))
      (node (ref "R20") (pin "1") (pinfunction "1_1") (pintype "passive"))
      (node (ref "R22") (pin "1") (pinfunction "1_1") (pintype "passive"))
      (node (ref "R23") (pin "1") (pinfunction "1_1") (pintype "passive"))
      (node (ref "R25") (pin "1") (pinfunction "1_1") (pintype "passive"))
      (node (ref "R26") (pin "1") (pinfunction "1_1") (pintype "passive"))
      (node (ref "R28") (pin "1") (pinfunction "1_1") (pintype "passive"))
      (node (ref "R29") (pin "1") (pinfunction "1_1") (pintype "passive"))
      (node (ref "R3") (pin "1") (pinfunction "1_1") (pintype "passive"))
      (node (ref "R31") (pin "1") (pinfunction "1_1") (pintype "passive"))
      (node (ref "R32") (pin "1") (pinfunction "1_1") (pintype "passive"))
      (node (ref "R35") (pin "2") (pinfunction "2_2") (pintype "passive"))
      (node (ref "R36") (pin "2") (pinfunction "2_2") (pintype "passive"))
      (node (ref "R37") (pin "2") (pinfunction "2_2") (pintype "passive"))
      (node (ref "R4") (pin "1") (pinfunction "1_1") (pintype "passive"))
      (node (ref "R8") (pin "1") (pinfunction "1_1") (pintype "passive"))
      (node (ref "S1") (pin "1") (pinfunction "1_1") (pintype "bidirectional"))
      (node (ref "S1") (pin "3") (pinfunction "1_3") (pintype "bidirectional"))
      (node (ref "TP12") (pin "P$1") (pinfunction "1_P$1") (pintype "bidirectional"))
      (node (ref "TP13") (pin "P$1") (pinfunction "1_P$1") (pintype "bidirectional"))
      (node (ref "U2") (pin "2") (pinfunction "GND_2") (pintype "power_in"))
      (node (ref "U3") (pin "2") (pinfunction "VSS_2") (pintype "power_in"))
      (node (ref "U4") (pin "15") (pinfunction "15_15") (pintype "passive"))
      (node (ref "U4") (pin "4") (pinfunction "CSN_4") (pintype "passive"))
      (node (ref "U5") (pin "10") (pinfunction "ADDR1_10") (pintype "bidirectional"))
      (node (ref "U5") (pin "17") (pinfunction "GND_17") (pintype "bidirectional"))
      (node (ref "U5") (pin "26") (pinfunction "ADDR0_26") (pintype "bidirectional"))
      (node (ref "U5") (pin "29") (pinfunction "GND_29") (pintype "bidirectional"))
      (node (ref "U5") (pin "3") (pinfunction "GND_3") (pintype "bidirectional"))
      (node (ref "U7") (pin "2") (pinfunction "GND_2") (pintype "power_in"))
      (node (ref "U7") (pin "THERM") (pinfunction "TP_THERM") (pintype "power_in"))
      (node (ref "U9") (pin "1") (pinfunction "GND_1") (pintype "bidirectional"))
      (node (ref "U9") (pin "15") (pinfunction "GND_15") (pintype "bidirectional"))
      (node (ref "U9") (pin "38") (pinfunction "GND_38") (pintype "bidirectional"))
      (node (ref "U9") (pin "GND") (pinfunction "GND_GND") (pintype "bidirectional"))
    )
    (net (code "23") (name "GREEN") (class "Default")
      (node (ref "R6") (pin "2") (pinfunction "2_2") (pintype "passive"))
      (node (ref "U5") (pin "22") (pinfunction "I/O[15]_22") (pintype "bidirectional"))
    )
    (net (code "24") (name "IO1-RST") (class "Default")
      (node (ref "TP26") (pin "P$1") (pinfunction "1_P$1") (pintype "bidirectional"))
      (node (ref "U5") (pin "23") (pinfunction "~{RESET}_23") (pintype "bidirectional"))
      (node (ref "U9") (pin "24") (pinfunction "2_24") (pintype "bidirectional"))
    )
    (net (code "25") (name "LEDEXT") (class "Default")
      (node (ref "J15") (pin "2") (pinfunction "2_2") (pintype "passive"))
      (node (ref "TP5") (pin "P$1") (pinfunction "1_P$1") (pintype "bidirectional"))
      (node (ref "U9") (pin "13") (pinfunction "14-IO_13") (pintype "bidirectional"))
    )
    (net (code "26") (name "Net-(C10-Pad1)") (class "Default")
      (node (ref "C10") (pin "1") (pinfunction "1_1") (pintype "passive"))
      (node (ref "Q4") (pin "1") (pinfunction "S_1") (pintype "bidirectional"))
      (node (ref "Q4") (pin "2") (pinfunction "S_2") (pintype "bidirectional"))
      (node (ref "Q4") (pin "3") (pinfunction "S_3") (pintype "bidirectional"))
      (node (ref "R17") (pin "2") (pinfunction "2_2") (pintype "passive"))
      (node (ref "R34") (pin "2") (pinfunction "2_2") (pintype "passive"))
    )
    (net (code "27") (name "Net-(D2-PadC)") (class "Default")
      (node (ref "D2") (pin "C") (pinfunction "C_C") (pintype "passive"))
      (node (ref "R2") (pin "1") (pinfunction "1_1") (pintype "passive"))
    )
    (net (code "28") (name "Net-(D3-A1)") (class "Default")
      (node (ref "C10") (pin "2") (pinfunction "2_2") (pintype "passive"))
      (node (ref "D3") (pin "1") (pinfunction "A1_1") (pintype "passive"))
      (node (ref "Q4") (pin "4") (pinfunction "G_4") (pintype "bidirectional"))
      (node (ref "Q5") (pin "3") (pinfunction "C_3") (pintype "passive"))
      (node (ref "R17") (pin "1") (pinfunction "1_1") (pintype "passive"))
    )
    (net (code "29") (name "Net-(D3-C)") (class "Default")
      (node (ref "D3") (pin "3") (pinfunction "C_3") (pintype "passive"))
      (node (ref "S1") (pin "2") (pinfunction "2_2") (pintype "bidirectional"))
      (node (ref "S1") (pin "4") (pinfunction "2_4") (pintype "bidirectional"))
    )
    (net (code "30") (name "Net-(D4-PadC)") (class "Default")
      (node (ref "D4") (pin "C") (pinfunction "C_C") (pintype "passive"))
      (node (ref "R37") (pin "1") (pinfunction "1_1") (pintype "passive"))
    )
    (net (code "31") (name "Net-(D5-PadC)") (class "Default")
      (node (ref "D5") (pin "C") (pinfunction "C_C") (pintype "passive"))
      (node (ref "R35") (pin "1") (pinfunction "1_1") (pintype "passive"))
    )
    (net (code "32") (name "Net-(D6-PadC)") (class "Default")
      (node (ref "D6") (pin "C") (pinfunction "C_C") (pintype "passive"))
      (node (ref "R36") (pin "1") (pinfunction "1_1") (pintype "passive"))
    )
    (net (code "33") (name "Net-(J3-1)") (class "Default")
      (node (ref "J3") (pin "2") (pinfunction "1_2") (pintype "passive"))
      (node (ref "M0") (pin "2") (pinfunction "A_OUT1_2") (pintype "output"))
      (node (ref "M0") (pin "7") (pinfunction "B_OUT1_7") (pintype "output"))
    )
    (net (code "34") (name "Net-(J3-2)") (class "Default")
      (node (ref "J3") (pin "1") (pinfunction "2_1") (pintype "passive"))
      (node (ref "M0") (pin "4") (pinfunction "A_OUT2_4") (pintype "output"))
      (node (ref "M0") (pin "5") (pinfunction "B_OUT2_5") (pintype "output"))
    )
    (net (code "35") (name "Net-(J4-1)") (class "Default")
      (node (ref "J4") (pin "2") (pinfunction "1_2") (pintype "passive"))
      (node (ref "M1") (pin "2") (pinfunction "A_OUT1_2") (pintype "output"))
      (node (ref "M1") (pin "7") (pinfunction "B_OUT1_7") (pintype "output"))
    )
    (net (code "36") (name "Net-(J4-2)") (class "Default")
      (node (ref "J4") (pin "1") (pinfunction "2_1") (pintype "passive"))
      (node (ref "M1") (pin "4") (pinfunction "A_OUT2_4") (pintype "output"))
      (node (ref "M1") (pin "5") (pinfunction "B_OUT2_5") (pintype "output"))
    )
    (net (code "37") (name "Net-(J5-1)") (class "Default")
      (node (ref "J5") (pin "2") (pinfunction "1_2") (pintype "passive"))
      (node (ref "M2") (pin "2") (pinfunction "A_OUT1_2") (pintype "output"))
      (node (ref "M2") (pin "7") (pinfunction "B_OUT1_7") (pintype "output"))
    )
    (net (code "38") (name "Net-(J5-2)") (class "Default")
      (node (ref "J5") (pin "1") (pinfunction "2_1") (pintype "passive"))
      (node (ref "M2") (pin "4") (pinfunction "A_OUT2_4") (pintype "output"))
      (node (ref "M2") (pin "5") (pinfunction "B_OUT2_5") (pintype "output"))
    )
    (net (code "39") (name "Net-(J6-1)") (class "Default")
      (node (ref "J6") (pin "2") (pinfunction "1_2") (pintype "passive"))
      (node (ref "M3") (pin "2") (pinfunction "A_OUT1_2") (pintype "output"))
      (node (ref "M3") (pin "7") (pinfunction "B_OUT1_7") (pintype "output"))
    )
    (net (code "40") (name "Net-(J6-2)") (class "Default")
      (node (ref "J6") (pin "1") (pinfunction "2_1") (pintype "passive"))
      (node (ref "M3") (pin "4") (pinfunction "A_OUT2_4") (pintype "output"))
      (node (ref "M3") (pin "5") (pinfunction "B_OUT2_5") (pintype "output"))
    )
    (net (code "41") (name "Net-(J7-1)") (class "Default")
      (node (ref "J7") (pin "2") (pinfunction "1_2") (pintype "passive"))
      (node (ref "M4") (pin "2") (pinfunction "A_OUT1_2") (pintype "output"))
      (node (ref "M4") (pin "7") (pinfunction "B_OUT1_7") (pintype "output"))
    )
    (net (code "42") (name "Net-(J7-2)") (class "Default")
      (node (ref "J7") (pin "1") (pinfunction "2_1") (pintype "passive"))
      (node (ref "M4") (pin "4") (pinfunction "A_OUT2_4") (pintype "output"))
      (node (ref "M4") (pin "5") (pinfunction "B_OUT2_5") (pintype "output"))
    )
    (net (code "43") (name "Net-(J8-1)") (class "Default")
      (node (ref "J8") (pin "2") (pinfunction "1_2") (pintype "passive"))
      (node (ref "M5") (pin "2") (pinfunction "A_OUT1_2") (pintype "output"))
      (node (ref "M5") (pin "7") (pinfunction "B_OUT1_7") (pintype "output"))
    )
    (net (code "44") (name "Net-(J8-2)") (class "Default")
      (node (ref "J8") (pin "1") (pinfunction "2_1") (pintype "passive"))
      (node (ref "M5") (pin "4") (pinfunction "A_OUT2_4") (pintype "output"))
      (node (ref "M5") (pin "5") (pinfunction "B_OUT2_5") (pintype "output"))
    )
    (net (code "45") (name "Net-(M0-A_ISENSE)") (class "Default")
      (node (ref "M0") (pin "3") (pinfunction "A_ISENSE_3") (pintype "bidirectional"))
      (node (ref "M0") (pin "6") (pinfunction "B_ISENSE_6") (pintype "bidirectional"))
      (node (ref "R15") (pin "2") (pinfunction "2_2") (pintype "passive"))
      (node (ref "R8") (pin "2") (pinfunction "2_2") (pintype "passive"))
    )
    (net (code "46") (name "Net-(M0-NSLEEP)") (class "Default")
      (node (ref "M0") (pin "1") (pinfunction "NSLEEP_1") (pintype "input"))
      (node (ref "R16") (pin "2") (pinfunction "2_2") (pintype "passive"))
    )
    (net (code "47") (name "Net-(M0-VCP)") (class "Default")
      (node (ref "C20") (pin "2") (pinfunction "2_2") (pintype "passive"))
      (node (ref "M0") (pin "11") (pinfunction "VCP_11") (pintype "bidirectional"))
    )
    (net (code "48") (name "Net-(M0-VINT)") (class "Default")
      (node (ref "C4") (pin "1") (pinfunction "1_1") (pintype "passive"))
      (node (ref "M0") (pin "14") (pinfunction "VINT_14") (pintype "power_in"))
    )
    (net (code "49") (name "Net-(M1-A_ISENSE)") (class "Default")
      (node (ref "M1") (pin "3") (pinfunction "A_ISENSE_3") (pintype "bidirectional"))
      (node (ref "M1") (pin "6") (pinfunction "B_ISENSE_6") (pintype "bidirectional"))
      (node (ref "R19") (pin "2") (pinfunction "2_2") (pintype "passive"))
      (node (ref "R20") (pin "2") (pinfunction "2_2") (pintype "passive"))
    )
    (net (code "50") (name "Net-(M1-NSLEEP)") (class "Default")
      (node (ref "M1") (pin "1") (pinfunction "NSLEEP_1") (pintype "input"))
      (node (ref "R21") (pin "2") (pinfunction "2_2") (pintype "passive"))
    )
    (net (code "51") (name "Net-(M1-VCP)") (class "Default")
      (node (ref "C16") (pin "2") (pinfunction "2_2") (pintype "passive"))
      (node (ref "M1") (pin "11") (pinfunction "VCP_11") (pintype "bidirectional"))
    )
    (net (code "52") (name "Net-(M1-VINT)") (class "Default")
      (node (ref "C17") (pin "1") (pinfunction "1_1") (pintype "passive"))
      (node (ref "M1") (pin "14") (pinfunction "VINT_14") (pintype "power_in"))
    )
    (net (code "53") (name "Net-(M2-A_ISENSE)") (class "Default")
      (node (ref "M2") (pin "3") (pinfunction "A_ISENSE_3") (pintype "bidirectional"))
      (node (ref "M2") (pin "6") (pinfunction "B_ISENSE_6") (pintype "bidirectional"))
      (node (ref "R22") (pin "2") (pinfunction "2_2") (pintype "passive"))
      (node (ref "R23") (pin "2") (pinfunction "2_2") (pintype "passive"))
    )
    (net (code "54") (name "Net-(M2-NSLEEP)") (class "Default")
      (node (ref "M2") (pin "1") (pinfunction "NSLEEP_1") (pintype "input"))
      (node (ref "R24") (pin "2") (pinfunction "2_2") (pintype "passive"))
    )
    (net (code "55") (name "Net-(M2-VCP)") (class "Default")
      (node (ref "C22") (pin "2") (pinfunction "2_2") (pintype "passive"))
      (node (ref "M2") (pin "11") (pinfunction "VCP_11") (pintype "bidirectional"))
    )
    (net (code "56") (name "Net-(M2-VINT)") (class "Default")
      (node (ref "C23") (pin "1") (pinfunction "1_1") (pintype "passive"))
      (node (ref "M2") (pin "14") (pinfunction "VINT_14") (pintype "power_in"))
    )
    (net (code "57") (name "Net-(M3-A_ISENSE)") (class "Default")
      (node (ref "M3") (pin "3") (pinfunction "A_ISENSE_3") (pintype "bidirectional"))
      (node (ref "M3") (pin "6") (pinfunction "B_ISENSE_6") (pintype "bidirectional"))
      (node (ref "R25") (pin "2") (pinfunction "2_2") (pintype "passive"))
      (node (ref "R26") (pin "2") (pinfunction "2_2") (pintype "passive"))
    )
    (net (code "58") (name "Net-(M3-NSLEEP)") (class "Default")
      (node (ref "M3") (pin "1") (pinfunction "NSLEEP_1") (pintype "input"))
      (node (ref "R27") (pin "2") (pinfunction "2_2") (pintype "passive"))
    )
    (net (code "59") (name "Net-(M3-VCP)") (class "Default")
      (node (ref "C26") (pin "2") (pinfunction "2_2") (pintype "passive"))
      (node (ref "M3") (pin "11") (pinfunction "VCP_11") (pintype "bidirectional"))
    )
    (net (code "60") (name "Net-(M3-VINT)") (class "Default")
      (node (ref "C27") (pin "1") (pinfunction "1_1") (pintype "passive"))
      (node (ref "M3") (pin "14") (pinfunction "VINT_14") (pintype "power_in"))
    )
    (net (code "61") (name "Net-(M4-A_ISENSE)") (class "Default")
      (node (ref "M4") (pin "3") (pinfunction "A_ISENSE_3") (pintype "bidirectional"))
      (node (ref "M4") (pin "6") (pinfunction "B_ISENSE_6") (pintype "bidirectional"))
      (node (ref "R28") (pin "2") (pinfunction "2_2") (pintype "passive"))
      (node (ref "R29") (pin "2") (pinfunction "2_2") (pintype "passive"))
    )
    (net (code "62") (name "Net-(M4-NSLEEP)") (class "Default")
      (node (ref "M4") (pin "1") (pinfunction "NSLEEP_1") (pintype "input"))
      (node (ref "R30") (pin "2") (pinfunction "2_2") (pintype "passive"))
    )
    (net (code "63") (name "Net-(M4-VCP)") (class "Default")
      (node (ref "C31") (pin "2") (pinfunction "2_2") (pintype "passive"))
      (node (ref "M4") (pin "11") (pinfunction "VCP_11") (pintype "bidirectional"))
    )
    (net (code "64") (name "Net-(M4-VINT)") (class "Default")
      (node (ref "C32") (pin "1") (pinfunction "1_1") (pintype "passive"))
      (node (ref "M4") (pin "14") (pinfunction "VINT_14") (pintype "power_in"))
    )
    (net (code "65") (name "Net-(M5-A_ISENSE)") (class "Default")
      (node (ref "M5") (pin "3") (pinfunction "A_ISENSE_3") (pintype "bidirectional"))
      (node (ref "M5") (pin "6") (pinfunction "B_ISENSE_6") (pintype "bidirectional"))
      (node (ref "R31") (pin "2") (pinfunction "2_2") (pintype "passive"))
      (node (ref "R32") (pin "2") (pinfunction "2_2") (pintype "passive"))
    )
    (net (code "66") (name "Net-(M5-NSLEEP)") (class "Default")
      (node (ref "M5") (pin "1") (pinfunction "NSLEEP_1") (pintype "input"))
      (node (ref "R33") (pin "2") (pinfunction "2_2") (pintype "passive"))
    )
    (net (code "67") (name "Net-(M5-VCP)") (class "Default")
      (node (ref "C35") (pin "2") (pinfunction "2_2") (pintype "passive"))
      (node (ref "M5") (pin "11") (pinfunction "VCP_11") (pintype "bidirectional"))
    )
    (net (code "68") (name "Net-(M5-VINT)") (class "Default")
      (node (ref "C36") (pin "1") (pinfunction "1_1") (pintype "passive"))
      (node (ref "M5") (pin "14") (pinfunction "VINT_14") (pintype "power_in"))
    )
    (net (code "69") (name "Net-(Q1-B)") (class "Default")
      (node (ref "Q1") (pin "1") (pinfunction "B_1") (pintype "passive"))
      (node (ref "R10") (pin "2") (pinfunction "2_2") (pintype "passive"))
    )
    (net (code "70") (name "Net-(Q2-B)") (class "Default")
      (node (ref "Q2") (pin "1") (pinfunction "B_1") (pintype "passive"))
      (node (ref "R9") (pin "2") (pinfunction "2_2") (pintype "passive"))
    )
    (net (code "71") (name "Net-(Q3-G)") (class "Default")
      (node (ref "D1") (pin "A") (pinfunction "A_A") (pintype "passive"))
      (node (ref "JP2") (pin "1") (pinfunction "1_1") (pintype "passive"))
      (node (ref "Q3") (pin "1") (pinfunction "G_1") (pintype "passive"))
      (node (ref "R12") (pin "2") (pinfunction "2_2") (pintype "passive"))
    )
    (net (code "72") (name "Net-(Q3-S)") (class "Default")
      (node (ref "C6") (pin "1") (pinfunction "1_1") (pintype "passive"))
      (node (ref "D1") (pin "C") (pinfunction "C_C") (pintype "passive"))
      (node (ref "Q3") (pin "2") (pinfunction "S_2") (pintype "passive"))
      (node (ref "U2") (pin "1") (pinfunction "IN_1") (pintype "power_in"))
      (node (ref "U2") (pin "3") (pinfunction "EN_3") (pintype "input"))
    )
    (net (code "73") (name "Net-(Q5-B)") (class "Default")
      (node (ref "Q5") (pin "1") (pinfunction "B_1") (pintype "passive"))
      (node (ref "R18") (pin "1") (pinfunction "1_1") (pintype "passive"))
    )
    (net (code "74") (name "Net-(TP7-1)") (class "Default")
      (node (ref "TP7") (pin "P$1") (pinfunction "1_P$1") (pintype "bidirectional"))
      (node (ref "U9") (pin "7") (pinfunction "35-IA_7") (pintype "bidirectional"))
    )
    (net (code "75") (name "Net-(TP9-1)") (class "Default")
      (node (ref "TP9") (pin "P$1") (pinfunction "1_P$1") (pintype "bidirectional"))
      (node (ref "U9") (pin "5") (pinfunction "39-I_5") (pintype "bidirectional"))
    )
    (net (code "76") (name "Net-(TP10-1)") (class "Default")
      (node (ref "TP10") (pin "P$1") (pinfunction "1_P$1") (pintype "bidirectional"))
      (node (ref "U9") (pin "4") (pinfunction "36-I_4") (pintype "bidirectional"))
    )
    (net (code "77") (name "Net-(U1-2)") (class "Default")
      (node (ref "R7") (pin "1") (pinfunction "1_1") (pintype "passive"))
      (node (ref "U1") (pin "BLUE") (pinfunction "2_BLUE") (pintype "passive"))
    )
    (net (code "78") (name "Net-(U1-3)") (class "Default")
      (node (ref "R6") (pin "1") (pinfunction "1_1") (pintype "passive"))
      (node (ref "U1") (pin "GREEN") (pinfunction "3_GREEN") (pintype "passive"))
    )
    (net (code "79") (name "Net-(U1-4)") (class "Default")
      (node (ref "R5") (pin "1") (pinfunction "1_1") (pintype "passive"))
      (node (ref "U1") (pin "RED") (pinfunction "4_RED") (pintype "passive"))
    )
    (net (code "80") (name "Net-(U3-PROG)") (class "Default")
      (node (ref "JP1") (pin "1") (pinfunction "1_1") (pintype "passive"))
      (node (ref "R4") (pin "2") (pinfunction "2_2") (pintype "passive"))
      (node (ref "U3") (pin "5") (pinfunction "PROG_5") (pintype "input"))
    )
    (net (code "81") (name "Net-(U3-STAT)") (class "Default")
      (node (ref "R2") (pin "2") (pinfunction "2_2") (pintype "passive"))
      (node (ref "U3") (pin "1") (pinfunction "STAT_1") (pintype "output"))
    )
    (net (code "82") (name "Net-(U4-CELL1)") (class "Default")
      (node (ref "C11") (pin "1") (pinfunction "1_1") (pintype "passive"))
      (node (ref "R1") (pin "2") (pinfunction "2_2") (pintype "passive"))
      (node (ref "U4") (pin "1") (pinfunction "REG3_1") (pintype "bidirectional"))
      (node (ref "U4") (pin "13") (pinfunction "CELLX_13") (pintype "passive"))
      (node (ref "U4") (pin "5") (pinfunction "VBATT_5") (pintype "passive"))
      (node (ref "U4") (pin "6") (pinfunction "CELL2_6") (pintype "bidirectional"))
      (node (ref "U4") (pin "7") (pinfunction "CELL1_7") (pintype "bidirectional"))
    )
    (net (code "83") (name "Net-(U4-REG2)") (class "Default")
      (node (ref "C1") (pin "1") (pinfunction "1_1") (pintype "passive"))
      (node (ref "U4") (pin "3") (pinfunction "REG2_3") (pintype "bidirectional"))
    )
    (net (code "84") (name "Net-(U7A-D+)") (class "Default")
      (node (ref "J1") (pin "D+") (pinfunction "D+_D+") (pintype "bidirectional"))
      (node (ref "U7") (pin "3") (pinfunction "D+_3") (pintype "bidirectional"))
    )
    (net (code "85") (name "Net-(U7A-D-)") (class "Default")
      (node (ref "J1") (pin "D-") (pinfunction "D-_D-") (pintype "bidirectional"))
      (node (ref "U7") (pin "4") (pinfunction "D-_4") (pintype "bidirectional"))
    )
    (net (code "86") (name "PWM0-1") (class "Default")
      (node (ref "J11") (pin "3") (pinfunction "3_3") (pintype "passive"))
      (node (ref "M0") (pin "16") (pinfunction "A_IN1_16") (pintype "input"))
      (node (ref "M0") (pin "9") (pinfunction "B_IN1_9") (pintype "input"))
      (node (ref "TP1") (pin "P$1") (pinfunction "1_P$1") (pintype "bidirectional"))
      (node (ref "U9") (pin "8") (pinfunction "32-IOA_8") (pintype "bidirectional"))
    )
    (net (code "87") (name "PWM0-2") (class "Default")
      (node (ref "J12") (pin "3") (pinfunction "3_3") (pintype "passive"))
      (node (ref "M0") (pin "10") (pinfunction "B_IN2_10") (pintype "input"))
      (node (ref "M0") (pin "15") (pinfunction "A_IN2_15") (pintype "input"))
      (node (ref "TP2") (pin "P$1") (pinfunction "1_P$1") (pintype "bidirectional"))
      (node (ref "U9") (pin "9") (pinfunction "33-IOA_9") (pintype "bidirectional"))
    )
    (net (code "88") (name "PWM1-1") (class "Default")
      (node (ref "J13") (pin "3") (pinfunction "3_3") (pintype "passive"))
      (node (ref "M1") (pin "16") (pinfunction "A_IN1_16") (pintype "input"))
      (node (ref "M1") (pin "9") (pinfunction "B_IN1_9") (pintype "input"))
      (node (ref "TP3") (pin "P$1") (pinfunction "1_P$1") (pintype "bidirectional"))
      (node (ref "U9") (pin "10") (pinfunction "25-IOD_10") (pintype "bidirectional"))
    )
    (net (code "89") (name "PWM1-2") (class "Default")
      (node (ref "J14") (pin "3") (pinfunction "3_3") (pintype "passive"))
      (node (ref "M1") (pin "10") (pinfunction "B_IN2_10") (pintype "input"))
      (node (ref "M1") (pin "15") (pinfunction "A_IN2_15") (pintype "input"))
      (node (ref "TP6") (pin "P$1") (pinfunction "1_P$1") (pintype "bidirectional"))
      (node (ref "U9") (pin "11") (pinfunction "26-IOD_11") (pintype "bidirectional"))
    )
    (net (code "90") (name "PWM2-1") (class "Default")
      (node (ref "M2") (pin "16") (pinfunction "A_IN1_16") (pintype "input"))
      (node (ref "M2") (pin "9") (pinfunction "B_IN1_9") (pintype "input"))
      (node (ref "TP17") (pin "P$1") (pinfunction "1_P$1") (pintype "bidirectional"))
      (node (ref "U9") (pin "12") (pinfunction "27-IO_12") (pintype "bidirectional"))
    )
    (net (code "91") (name "PWM2-2") (class "Default")
      (node (ref "M2") (pin "10") (pinfunction "B_IN2_10") (pintype "input"))
      (node (ref "M2") (pin "15") (pinfunction "A_IN2_15") (pintype "input"))
      (node (ref "TP23") (pin "P$1") (pinfunction "1_P$1") (pintype "bidirectional"))
      (node (ref "U9") (pin "16") (pinfunction "13-IO_16") (pintype "bidirectional"))
    )
    (net (code "92") (name "PWM3-1") (class "Default")
      (node (ref "M3") (pin "16") (pinfunction "A_IN1_16") (pintype "input"))
      (node (ref "M3") (pin "9") (pinfunction "B_IN1_9") (pintype "input"))
      (node (ref "TP16") (pin "P$1") (pinfunction "1_P$1") (pintype "bidirectional"))
      (node (ref "U9") (pin "26") (pinfunction "4-IO_26") (pintype "bidirectional"))
    )
    (net (code "93") (name "PWM3-2") (class "Default")
      (node (ref "M3") (pin "10") (pinfunction "B_IN2_10") (pintype "input"))
      (node (ref "M3") (pin "15") (pinfunction "A_IN2_15") (pintype "input"))
      (node (ref "TP15") (pin "P$1") (pinfunction "1_P$1") (pintype "bidirectional"))
      (node (ref "U9") (pin "27") (pinfunction "16-IO_27") (pintype "bidirectional"))
    )
    (net (code "94") (name "PWM4-1") (class "Default")
      (node (ref "M4") (pin "16") (pinfunction "A_IN1_16") (pintype "input"))
      (node (ref "M4") (pin "9") (pinfunction "B_IN1_9") (pintype "input"))
      (node (ref "TP22") (pin "P$1") (pinfunction "1_P$1") (pintype "bidirectional"))
      (node (ref "U9") (pin "28") (pinfunction "17-IO_28") (pintype "bidirectional"))
    )
    (net (code "95") (name "PWM4-2") (class "Default")
      (node (ref "M4") (pin "10") (pinfunction "B_IN2_10") (pintype "input"))
      (node (ref "M4") (pin "15") (pinfunction "A_IN2_15") (pintype "input"))
      (node (ref "TP21") (pin "P$1") (pinfunction "1_P$1") (pintype "bidirectional"))
      (node (ref "U9") (pin "30") (pinfunction "18-IO_30") (pintype "bidirectional"))
    )
    (net (code "96") (name "PWM5-1") (class "Default")
      (node (ref "M5") (pin "16") (pinfunction "A_IN1_16") (pintype "input"))
      (node (ref "M5") (pin "9") (pinfunction "B_IN1_9") (pintype "input"))
      (node (ref "TP20") (pin "P$1") (pinfunction "1_P$1") (pintype "bidirectional"))
      (node (ref "U9") (pin "31") (pinfunction "19-IO_31") (pintype "bidirectional"))
    )
    (net (code "97") (name "PWM5-2") (class "Default")
      (node (ref "M5") (pin "10") (pinfunction "B_IN2_10") (pintype "input"))
      (node (ref "M5") (pin "15") (pinfunction "A_IN2_15") (pintype "input"))
      (node (ref "TP14") (pin "P$1") (pinfunction "1_P$1") (pintype "bidirectional"))
      (node (ref "U9") (pin "37") (pinfunction "23-IO_37") (pintype "bidirectional"))
    )
    (net (code "98") (name "PWR") (class "Default")
      (node (ref "R18") (pin "2") (pinfunction "2_2") (pintype "passive"))
      (node (ref "TP4") (pin "P$1") (pinfunction "1_P$1") (pintype "bidirectional"))
      (node (ref "U9") (pin "14") (pinfunction "12_14") (pintype "bidirectional"))
    )
    (net (code "99") (name "RED") (class "Default")
      (node (ref "R5") (pin "2") (pinfunction "2_2") (pintype "passive"))
      (node (ref "U5") (pin "20") (pinfunction "I/O[13]_20") (pintype "bidirectional"))
    )
    (net (code "100") (name "RTS") (class "Default")
      (node (ref "Q1") (pin "2") (pinfunction "E_2") (pintype "passive"))
      (node (ref "R9") (pin "1") (pinfunction "1_1") (pintype "passive"))
      (node (ref "U7") (pin "19") (pinfunction "RTS_19") (pintype "output"))
    )
    (net (code "101") (name "RX") (class "Default")
      (node (ref "U7") (pin "21") (pinfunction "TXD_21") (pintype "output"))
      (node (ref "U9") (pin "34") (pinfunction "RX_34") (pintype "bidirectional"))
    )
    (net (code "102") (name "S1-SIG") (class "Default")
      (node (ref "J9") (pin "3") (pinfunction "3_3") (pintype "passive"))
      (node (ref "TP24") (pin "P$1") (pinfunction "1_P$1") (pintype "bidirectional"))
      (node (ref "U9") (pin "23") (pinfunction "15_23") (pintype "bidirectional"))
    )
    (net (code "103") (name "S2-SIG") (class "Default")
      (node (ref "J10") (pin "3") (pinfunction "3_3") (pintype "passive"))
      (node (ref "TP25") (pin "P$1") (pinfunction "1_P$1") (pintype "bidirectional"))
      (node (ref "U9") (pin "29") (pinfunction "5_29") (pintype "bidirectional"))
    )
    (net (code "104") (name "SCL") (class "Default")
      (node (ref "R14") (pin "2") (pinfunction "2_2") (pintype "passive"))
      (node (ref "TP18") (pin "P$1") (pinfunction "1_P$1") (pintype "bidirectional"))
      (node (ref "U4") (pin "11") (pinfunction "OD/SCL_11") (pintype "passive"))
      (node (ref "U5") (pin "25") (pinfunction "SCL_25") (pintype "bidirectional"))
      (node (ref "U9") (pin "36") (pinfunction "22-IO_36") (pintype "bidirectional"))
    )
    (net (code "105") (name "SDA") (class "Default")
      (node (ref "R13") (pin "1") (pinfunction "1_1") (pintype "passive"))
      (node (ref "TP19") (pin "P$1") (pinfunction "1_P$1") (pintype "bidirectional"))
      (node (ref "U4") (pin "12") (pinfunction "DQ/SDA_12") (pintype "passive"))
      (node (ref "U5") (pin "24") (pinfunction "SDA_24") (pintype "bidirectional"))
      (node (ref "U9") (pin "33") (pinfunction "21-IO_33") (pintype "bidirectional"))
    )
    (net (code "106") (name "TX") (class "Default")
      (node (ref "U7") (pin "20") (pinfunction "RXD_20") (pintype "input"))
      (node (ref "U9") (pin "35") (pinfunction "TX_35") (pintype "bidirectional"))
    )
    (net (code "107") (name "VBAT") (class "Default")
      (node (ref "C12") (pin "1") (pinfunction "1_1") (pintype "passive"))
      (node (ref "C14") (pin "+") (pinfunction "+_+") (pintype "passive"))
      (node (ref "C16") (pin "1") (pinfunction "1_1") (pintype "passive"))
      (node (ref "C18") (pin "1") (pinfunction "1_1") (pintype "passive"))
      (node (ref "C19") (pin "+") (pinfunction "+_+") (pintype "passive"))
      (node (ref "C20") (pin "1") (pinfunction "1_1") (pintype "passive"))
      (node (ref "C22") (pin "1") (pinfunction "1_1") (pintype "passive"))
      (node (ref "C24") (pin "1") (pinfunction "1_1") (pintype "passive"))
      (node (ref "C25") (pin "+") (pinfunction "+_+") (pintype "passive"))
      (node (ref "C26") (pin "1") (pinfunction "1_1") (pintype "passive"))
      (node (ref "C28") (pin "+") (pinfunction "+_+") (pintype "passive"))
      (node (ref "C29") (pin "1") (pinfunction "1_1") (pintype "passive"))
      (node (ref "C30") (pin "+") (pinfunction "+_+") (pintype "passive"))
      (node (ref "C31") (pin "1") (pinfunction "1_1") (pintype "passive"))
      (node (ref "C33") (pin "1") (pinfunction "1_1") (pintype "passive"))
      (node (ref "C34") (pin "+") (pinfunction "+_+") (pintype "passive"))
      (node (ref "C35") (pin "1") (pinfunction "1_1") (pintype "passive"))
      (node (ref "C5") (pin "1") (pinfunction "1_1") (pintype "passive"))
      (node (ref "D5") (pin "A") (pinfunction "A_A") (pintype "passive"))
      (node (ref "J10") (pin "2") (pinfunction "2_2") (pintype "passive"))
      (node (ref "J11") (pin "2") (pinfunction "2_2") (pintype "passive"))
      (node (ref "J12") (pin "2") (pinfunction "2_2") (pintype "passive"))
      (node (ref "J13") (pin "2") (pinfunction "2_2") (pintype "passive"))
      (node (ref "J14") (pin "2") (pinfunction "2_2") (pintype "passive"))
      (node (ref "J9") (pin "2") (pinfunction "2_2") (pintype "passive"))
      (node (ref "M0") (pin "12") (pinfunction "VM_12") (pintype "power_in"))
      (node (ref "M1") (pin "12") (pinfunction "VM_12") (pintype "power_in"))
      (node (ref "M2") (pin "12") (pinfunction "VM_12") (pintype "power_in"))
      (node (ref "M3") (pin "12") (pinfunction "VM_12") (pintype "power_in"))
      (node (ref "M4") (pin "12") (pinfunction "VM_12") (pintype "power_in"))
      (node (ref "M5") (pin "12") (pinfunction "VM_12") (pintype "power_in"))
      (node (ref "Q3") (pin "3") (pinfunction "D_3") (pintype "passive"))
      (node (ref "Q4") (pin "5") (pinfunction "D_5") (pintype "bidirectional"))
      (node (ref "Q4") (pin "6") (pinfunction "D_6") (pintype "bidirectional"))
      (node (ref "Q4") (pin "7") (pinfunction "D_7") (pintype "bidirectional"))
      (node (ref "Q4") (pin "8") (pinfunction "D_8") (pintype "bidirectional"))
      (node (ref "R1") (pin "1") (pinfunction "1_1") (pintype "passive"))
      (node (ref "R16") (pin "1") (pinfunction "1_1") (pintype "passive"))
      (node (ref "R21") (pin "1") (pinfunction "1_1") (pintype "passive"))
      (node (ref "R24") (pin "1") (pinfunction "1_1") (pintype "passive"))
      (node (ref "R27") (pin "1") (pinfunction "1_1") (pintype "passive"))
      (node (ref "R30") (pin "1") (pinfunction "1_1") (pintype "passive"))
      (node (ref "R33") (pin "1") (pinfunction "1_1") (pintype "passive"))
    )
    (net (code "108") (name "VUSB") (class "Default")
      (node (ref "C9") (pin "1") (pinfunction "1_1") (pintype "passive"))
      (node (ref "D2") (pin "A") (pinfunction "A_A") (pintype "passive"))
      (node (ref "D4") (pin "A") (pinfunction "A_A") (pintype "passive"))
      (node (ref "J1") (pin "VBUS") (pinfunction "VBUS_VBUS") (pintype "power_in"))
      (node (ref "JP1") (pin "2") (pinfunction "2_2") (pintype "passive"))
      (node (ref "JP2") (pin "2") (pinfunction "2_2") (pintype "passive"))
      (node (ref "U3") (pin "4") (pinfunction "VDD_4") (pintype "power_in"))
      (node (ref "U7") (pin "8") (pinfunction "VBUS_8") (pintype "power_in"))
    )
    (net (code "109") (name "unconnected-(J1-PadID)") (class "Default")
      (node (ref "J1") (pin "ID") (pinfunction "ID_ID") (pintype "bidirectional"))
    )
    (net (code "110") (name "unconnected-(M0-NFAULT-Pad8)") (class "Default")
      (node (ref "M0") (pin "8") (pinfunction "NFAULT_8") (pintype "bidirectional"))
    )
    (net (code "111") (name "unconnected-(M1-NFAULT-Pad8)") (class "Default")
      (node (ref "M1") (pin "8") (pinfunction "NFAULT_8") (pintype "bidirectional"))
    )
    (net (code "112") (name "unconnected-(M2-NFAULT-Pad8)") (class "Default")
      (node (ref "M2") (pin "8") (pinfunction "NFAULT_8") (pintype "bidirectional"))
    )
    (net (code "113") (name "unconnected-(M3-NFAULT-Pad8)") (class "Default")
      (node (ref "M3") (pin "8") (pinfunction "NFAULT_8") (pintype "bidirectional"))
    )
    (net (code "114") (name "unconnected-(M4-NFAULT-Pad8)") (class "Default")
      (node (ref "M4") (pin "8") (pinfunction "NFAULT_8") (pintype "bidirectional"))
    )
    (net (code "115") (name "unconnected-(M5-NFAULT-Pad8)") (class "Default")
      (node (ref "M5") (pin "8") (pinfunction "NFAULT_8") (pintype "bidirectional"))
    )
    (net (code "116") (name "unconnected-(U2-P4-Pad4)") (class "Default")
      (node (ref "U2") (pin "4") (pinfunction "P4_4") (pintype "bidirectional"))
    )
    (net (code "117") (name "unconnected-(U4-AIN1-Pad9)") (class "Default")
      (node (ref "U4") (pin "9") (pinfunction "AIN1_9") (pintype "input"))
    )
    (net (code "118") (name "unconnected-(U4-AIN2-Pad10)") (class "Default")
      (node (ref "U4") (pin "10") (pinfunction "AIN2_10") (pintype "input"))
    )
    (net (code "119") (name "unconnected-(U4-ALRT1-Pad8)") (class "Default")
      (node (ref "U4") (pin "8") (pinfunction "ALRT1_8") (pintype "passive"))
    )
    (net (code "120") (name "unconnected-(U4-THRM-Pad14)") (class "Default")
      (node (ref "U4") (pin "14") (pinfunction "THRM_14") (pintype "passive"))
    )
    (net (code "121") (name "unconnected-(U5-OSCIO-Pad11)") (class "Default")
      (node (ref "U5") (pin "11") (pinfunction "OSCIO_11") (pintype "bidirectional"))
    )
    (net (code "122") (name "unconnected-(U5-~{INT}-Pad9)") (class "Default")
      (node (ref "U5") (pin "9") (pinfunction "~{INT}_9") (pintype "bidirectional"))
    )
    (net (code "123") (name "unconnected-(U7A-#RST-Pad9)") (class "Default")
      (node (ref "U7") (pin "9") (pinfunction "#RST_9") (pintype "bidirectional"))
    )
    (net (code "124") (name "unconnected-(U7A-#SUSPEND-Pad15)") (class "Default")
      (node (ref "U7") (pin "15") (pinfunction "#SUSPEND_15") (pintype "output"))
    )
    (net (code "125") (name "unconnected-(U7A-CTS-Pad18)") (class "Default")
      (node (ref "U7") (pin "18") (pinfunction "CTS_18") (pintype "input"))
    )
    (net (code "126") (name "unconnected-(U7A-DCD-Pad24)") (class "Default")
      (node (ref "U7") (pin "24") (pinfunction "DCD_24") (pintype "input"))
    )
    (net (code "127") (name "unconnected-(U7A-DSR-Pad22)") (class "Default")
      (node (ref "U7") (pin "22") (pinfunction "DSR_22") (pintype "input"))
    )
    (net (code "128") (name "unconnected-(U7A-GPIO0{slash}TXLED-Pad14)") (class "Default")
      (node (ref "U7") (pin "14") (pinfunction "GPIO0/TXLED_14") (pintype "bidirectional"))
    )
    (net (code "129") (name "unconnected-(U7A-GPIO1{slash}RXLED-Pad13)") (class "Default")
      (node (ref "U7") (pin "13") (pinfunction "GPIO1/RXLED_13") (pintype "bidirectional"))
    )
    (net (code "130") (name "unconnected-(U7A-GPIO2-Pad12)") (class "Default")
      (node (ref "U7") (pin "12") (pinfunction "GPIO2_12") (pintype "bidirectional"))
    )
    (net (code "131") (name "unconnected-(U7A-GPIO3-Pad11)") (class "Default")
      (node (ref "U7") (pin "11") (pinfunction "GPIO3_11") (pintype "bidirectional"))
    )
    (net (code "132") (name "unconnected-(U7A-NC-Pad10)") (class "Default")
      (node (ref "U7") (pin "10") (pinfunction "NC_10") (pintype "no_connect"))
    )
    (net (code "133") (name "unconnected-(U7A-RI-Pad1)") (class "Default")
      (node (ref "U7") (pin "1") (pinfunction "RI_1") (pintype "input"))
    )
    (net (code "134") (name "unconnected-(U7A-SUSPEND-Pad17)") (class "Default")
      (node (ref "U7") (pin "17") (pinfunction "SUSPEND_17") (pintype "output"))
    )
    (net (code "135") (name "unconnected-(U7A-VPP-Pad16)") (class "Default")
      (node (ref "U7") (pin "16") (pinfunction "VPP_16") (pintype "bidirectional"))
    )
    (net (code "136") (name "unconnected-(U9-NC-Pad32)") (class "Default")
      (node (ref "U9") (pin "32") (pinfunction "NC_32") (pintype "bidirectional"))
    )
    (net (code "137") (name "unconnected-(U9-SCK-Pad20)") (class "Default")
      (node (ref "U9") (pin "20") (pinfunction "SCK_20") (pintype "bidirectional"))
    )
    (net (code "138") (name "unconnected-(U9-SCS-Pad19)") (class "Default")
      (node (ref "U9") (pin "19") (pinfunction "SCS_19") (pintype "bidirectional"))
    )
    (net (code "139") (name "unconnected-(U9-SDI-Pad22)") (class "Default")
      (node (ref "U9") (pin "22") (pinfunction "SDI_22") (pintype "bidirectional"))
    )
    (net (code "140") (name "unconnected-(U9-SDO-Pad21)") (class "Default")
      (node (ref "U9") (pin "21") (pinfunction "SDO_21") (pintype "bidirectional"))
    )
    (net (code "141") (name "unconnected-(U9-SHD-Pad17)") (class "Default")
      (node (ref "U9") (pin "17") (pinfunction "SHD_17") (pintype "bidirectional"))
    )
    (net (code "142") (name "unconnected-(U9-SWP-Pad18)") (class "Default")
      (node (ref "U9") (pin "18") (pinfunction "SWP_18") (pintype "bidirectional"))
    )
  )
)
